# driver_board.net
KiCad netlist of a schematic drawn in EAGLE
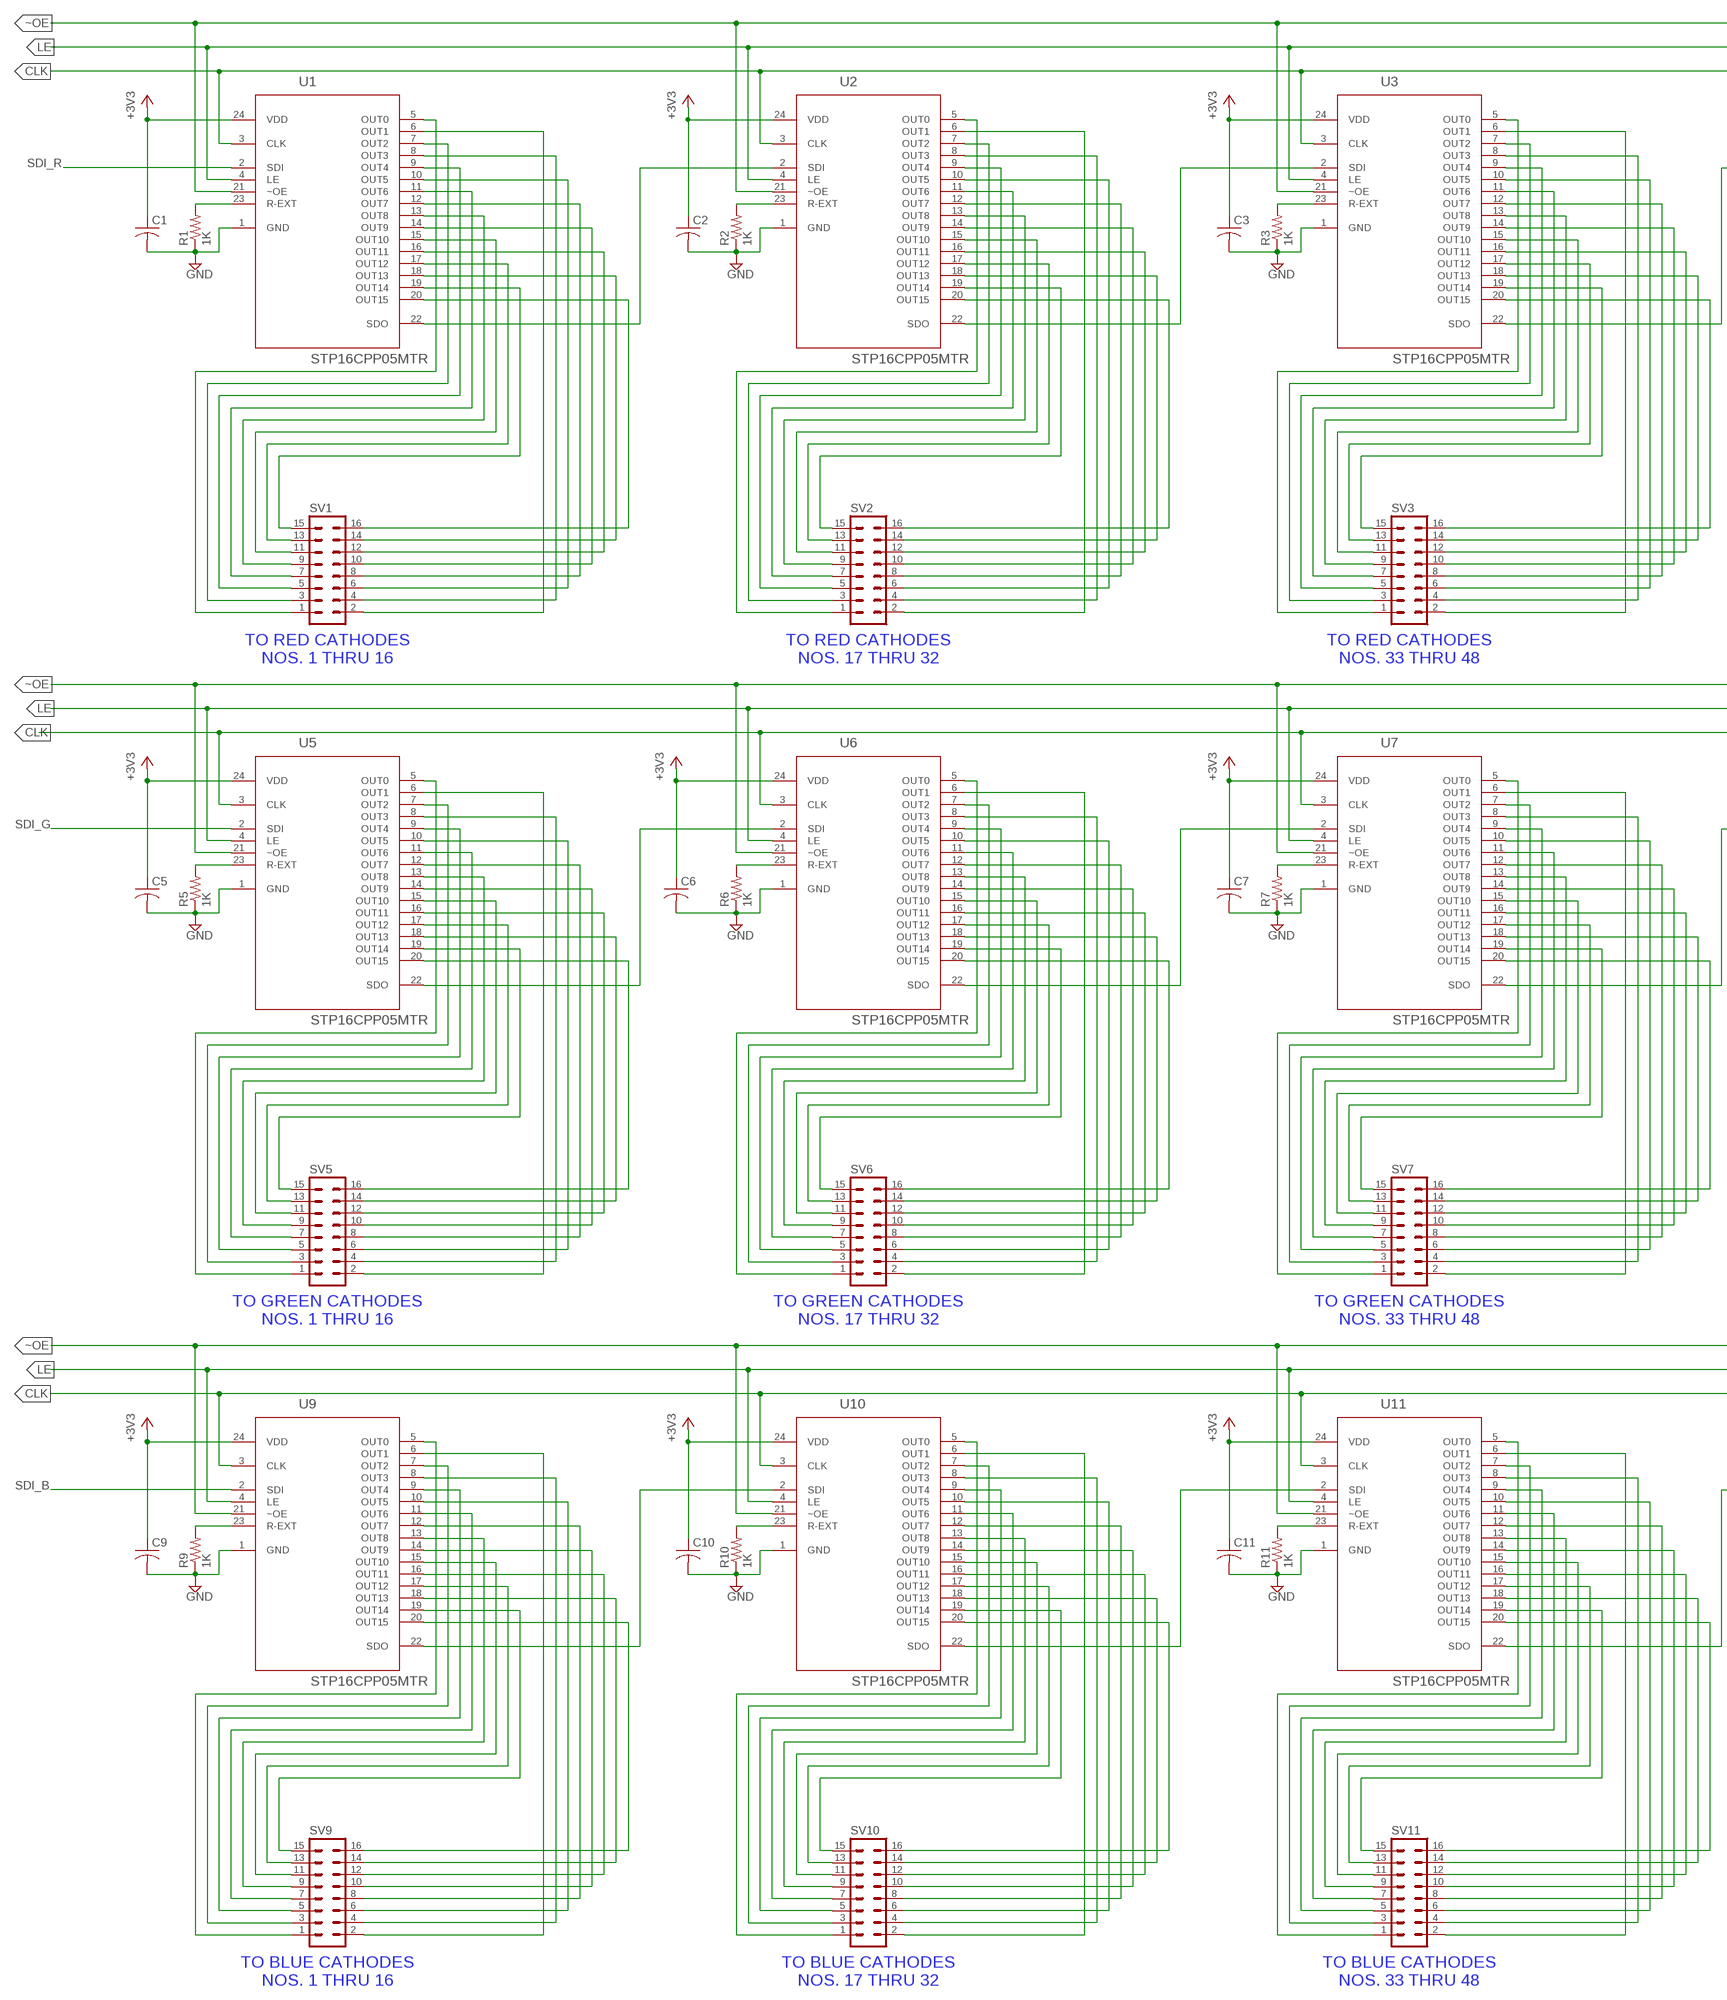
[diagram p0: schematic, sheet 1, part 1 of 2]
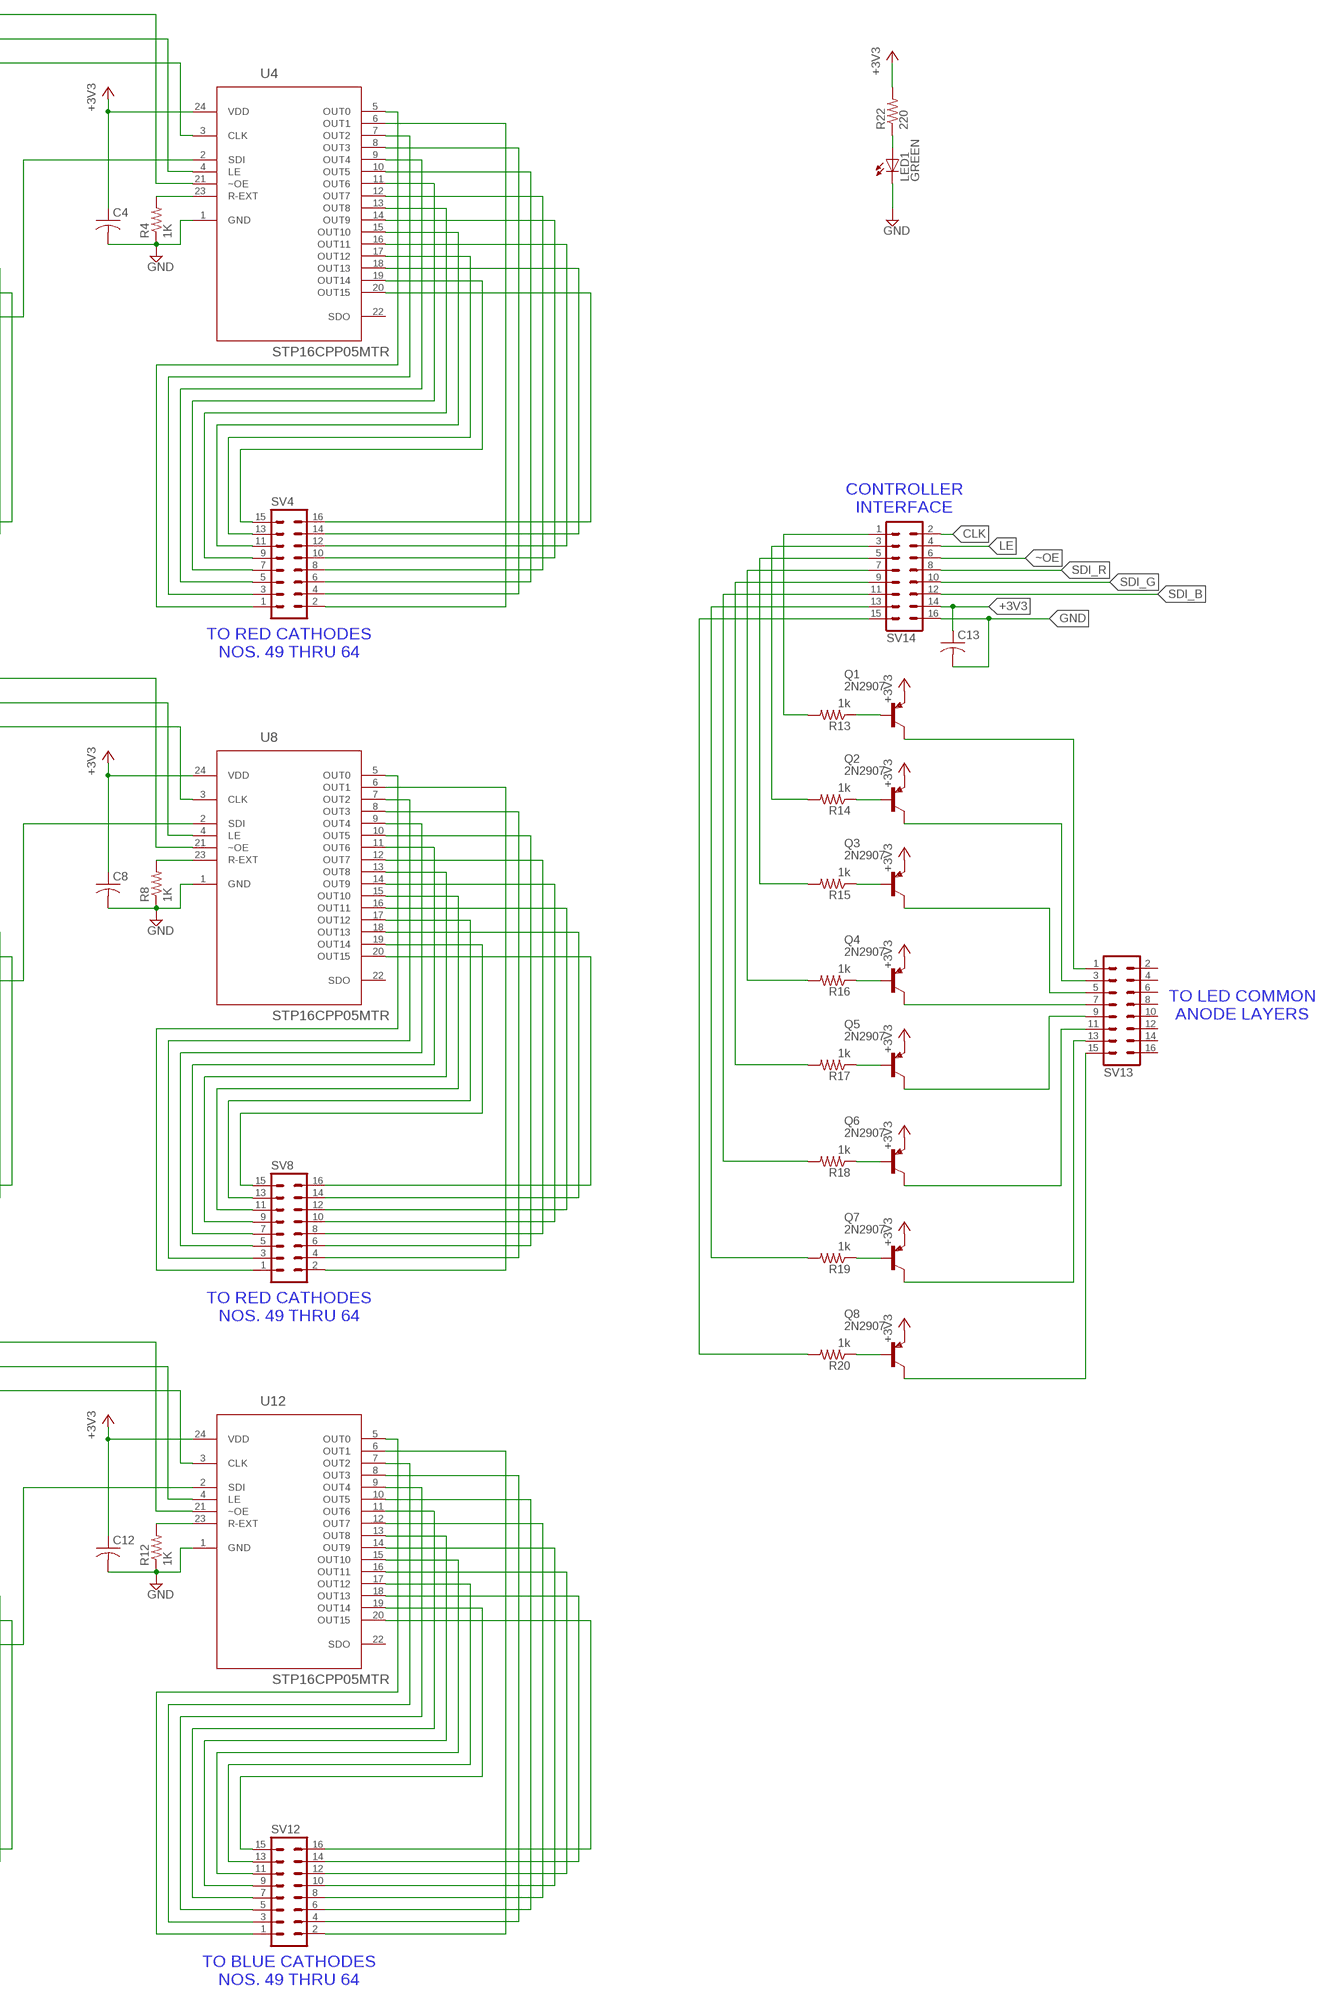
[diagram p1: schematic, sheet 1, part 2 of 2]

(export (version "E")
  (design (tool "Eeschema 10.0.6"))
  (components
    (comp (ref "C1")
      (value "C-USC0805")
      (footprint "eagle-import:C0805")
      (fields (field (name "MF") "AVX CORPORATION") (field (name "MPN") "0805ZC105KAT2A"))
      (libsource (lib "eagle-import") (part "C-USC0805"))
    )
    (comp (ref "C2")
      (value "C-USC0805")
      (footprint "eagle-import:C0805")
      (fields (field (name "MF") "AVX CORPORATION") (field (name "MPN") "0805ZC105KAT2A"))
      (libsource (lib "eagle-import") (part "C-USC0805"))
    )
    (comp (ref "C3")
      (value "C-USC0805")
      (footprint "eagle-import:C0805")
      (fields (field (name "MF") "AVX CORPORATION") (field (name "MPN") "0805ZC105KAT2A"))
      (libsource (lib "eagle-import") (part "C-USC0805"))
    )
    (comp (ref "C4")
      (value "C-USC0805")
      (footprint "eagle-import:C0805")
      (fields (field (name "MF") "AVX CORPORATION") (field (name "MPN") "0805ZC105KAT2A"))
      (libsource (lib "eagle-import") (part "C-USC0805"))
    )
    (comp (ref "C5")
      (value "C-USC0805")
      (footprint "eagle-import:C0805")
      (fields (field (name "MF") "AVX CORPORATION") (field (name "MPN") "0805ZC105KAT2A"))
      (libsource (lib "eagle-import") (part "C-USC0805"))
    )
    (comp (ref "C6")
      (value "C-USC0805")
      (footprint "eagle-import:C0805")
      (fields (field (name "MF") "AVX CORPORATION") (field (name "MPN") "0805ZC105KAT2A"))
      (libsource (lib "eagle-import") (part "C-USC0805"))
    )
    (comp (ref "C7")
      (value "C-USC0805")
      (footprint "eagle-import:C0805")
      (fields (field (name "MF") "AVX CORPORATION") (field (name "MPN") "0805ZC105KAT2A"))
      (libsource (lib "eagle-import") (part "C-USC0805"))
    )
    (comp (ref "C8")
      (value "C-USC0805")
      (footprint "eagle-import:C0805")
      (fields (field (name "MF") "AVX CORPORATION") (field (name "MPN") "0805ZC105KAT2A"))
      (libsource (lib "eagle-import") (part "C-USC0805"))
    )
    (comp (ref "C9")
      (value "C-USC0805")
      (footprint "eagle-import:C0805")
      (fields (field (name "MF") "AVX CORPORATION") (field (name "MPN") "0805ZC105KAT2A"))
      (libsource (lib "eagle-import") (part "C-USC0805"))
    )
    (comp (ref "C10")
      (value "C-USC0805")
      (footprint "eagle-import:C0805")
      (fields (field (name "MF") "AVX CORPORATION") (field (name "MPN") "0805ZC105KAT2A"))
      (libsource (lib "eagle-import") (part "C-USC0805"))
    )
    (comp (ref "C11")
      (value "C-USC0805")
      (footprint "eagle-import:C0805")
      (fields (field (name "MF") "AVX CORPORATION") (field (name "MPN") "0805ZC105KAT2A"))
      (libsource (lib "eagle-import") (part "C-USC0805"))
    )
    (comp (ref "C12")
      (value "C-USC0805")
      (footprint "eagle-import:C0805")
      (fields (field (name "MF") "AVX CORPORATION") (field (name "MPN") "0805ZC105KAT2A"))
      (libsource (lib "eagle-import") (part "C-USC0805"))
    )
    (comp (ref "C13")
      (value "C-USC0805")
      (footprint "eagle-import:C0805")
      (fields (field (name "MF") "AVX CORPORATION") (field (name "MPN") "0805ZC105KAT2A"))
      (libsource (lib "eagle-import") (part "C-USC0805"))
    )
    (comp (ref "LED1")
      (value "GREEN")
      (footprint "eagle-import:LED5MM")
      (fields (field (name "MF") "SLI (CML/IDI)") (field (name "MPN") "CMD17-21VGD/TR8"))
      (libsource (lib "eagle-import") (part "LED5MM"))
    )
    (comp (ref "Q1")
      (value "2N2907")
      (footprint "eagle-import:TO92-EBC-OVAL")
      (fields (field (name "MF") "ON SEMICONDUCTOR") (field (name "MPN") "TIP32BG"))
      (libsource (lib "eagle-import") (part "2N2907"))
    )
    (comp (ref "Q2")
      (value "2N2907")
      (footprint "eagle-import:TO92-EBC-OVAL")
      (fields (field (name "MF") "ON SEMICONDUCTOR") (field (name "MPN") "TIP32BG"))
      (libsource (lib "eagle-import") (part "2N2907"))
    )
    (comp (ref "Q3")
      (value "2N2907")
      (footprint "eagle-import:TO92-EBC-OVAL")
      (fields (field (name "MF") "ON SEMICONDUCTOR") (field (name "MPN") "TIP32BG"))
      (libsource (lib "eagle-import") (part "2N2907"))
    )
    (comp (ref "Q4")
      (value "2N2907")
      (footprint "eagle-import:TO92-EBC-OVAL")
      (fields (field (name "MF") "ON SEMICONDUCTOR") (field (name "MPN") "TIP32BG"))
      (libsource (lib "eagle-import") (part "2N2907"))
    )
    (comp (ref "Q5")
      (value "2N2907")
      (footprint "eagle-import:TO92-EBC-OVAL")
      (fields (field (name "MF") "ON SEMICONDUCTOR") (field (name "MPN") "TIP32BG"))
      (libsource (lib "eagle-import") (part "2N2907"))
    )
    (comp (ref "Q6")
      (value "2N2907")
      (footprint "eagle-import:TO92-EBC-OVAL")
      (fields (field (name "MF") "ON SEMICONDUCTOR") (field (name "MPN") "TIP32BG"))
      (libsource (lib "eagle-import") (part "2N2907"))
    )
    (comp (ref "Q7")
      (value "2N2907")
      (footprint "eagle-import:TO92-EBC-OVAL")
      (fields (field (name "MF") "ON SEMICONDUCTOR") (field (name "MPN") "TIP32BG"))
      (libsource (lib "eagle-import") (part "2N2907"))
    )
    (comp (ref "Q8")
      (value "2N2907")
      (footprint "eagle-import:TO92-EBC-OVAL")
      (fields (field (name "MF") "ON SEMICONDUCTOR") (field (name "MPN") "TIP32BG"))
      (libsource (lib "eagle-import") (part "2N2907"))
    )
    (comp (ref "R1")
      (value "1K")
      (footprint "eagle-import:R0805")
      (fields (field (name "MPN") "MC01W080511K"))
      (libsource (lib "eagle-import") (part "R-US_R0805"))
    )
    (comp (ref "R2")
      (value "1K")
      (footprint "eagle-import:R0805")
      (fields (field (name "MPN") "MC01W080511K"))
      (libsource (lib "eagle-import") (part "R-US_R0805"))
    )
    (comp (ref "R3")
      (value "1K")
      (footprint "eagle-import:R0805")
      (fields (field (name "MPN") "MC01W080511K"))
      (libsource (lib "eagle-import") (part "R-US_R0805"))
    )
    (comp (ref "R4")
      (value "1K")
      (footprint "eagle-import:R0805")
      (fields (field (name "MPN") "MC01W080511K"))
      (libsource (lib "eagle-import") (part "R-US_R0805"))
    )
    (comp (ref "R5")
      (value "1K")
      (footprint "eagle-import:R0805")
      (fields (field (name "MPN") "MC01W080511K"))
      (libsource (lib "eagle-import") (part "R-US_R0805"))
    )
    (comp (ref "R6")
      (value "1K")
      (footprint "eagle-import:R0805")
      (fields (field (name "MPN") "MC01W080511K"))
      (libsource (lib "eagle-import") (part "R-US_R0805"))
    )
    (comp (ref "R7")
      (value "1K")
      (footprint "eagle-import:R0805")
      (fields (field (name "MPN") "MC01W080511K"))
      (libsource (lib "eagle-import") (part "R-US_R0805"))
    )
    (comp (ref "R8")
      (value "1K")
      (footprint "eagle-import:R0805")
      (fields (field (name "MPN") "MC01W080511K"))
      (libsource (lib "eagle-import") (part "R-US_R0805"))
    )
    (comp (ref "R9")
      (value "1K")
      (footprint "eagle-import:R0805")
      (fields (field (name "MPN") "MC01W080511K"))
      (libsource (lib "eagle-import") (part "R-US_R0805"))
    )
    (comp (ref "R10")
      (value "1K")
      (footprint "eagle-import:R0805")
      (fields (field (name "MPN") "MC01W080511K"))
      (libsource (lib "eagle-import") (part "R-US_R0805"))
    )
    (comp (ref "R11")
      (value "1K")
      (footprint "eagle-import:R0805")
      (fields (field (name "MPN") "MC01W080511K"))
      (libsource (lib "eagle-import") (part "R-US_R0805"))
    )
    (comp (ref "R12")
      (value "1K")
      (footprint "eagle-import:R0805")
      (fields (field (name "MPN") "MC01W080511K"))
      (libsource (lib "eagle-import") (part "R-US_R0805"))
    )
    (comp (ref "R13")
      (value "1k")
      (footprint "eagle-import:R0805")
      (libsource (lib "eagle-import") (part "R-US_R0805"))
    )
    (comp (ref "R14")
      (value "1k")
      (footprint "eagle-import:R0805")
      (libsource (lib "eagle-import") (part "R-US_R0805"))
    )
    (comp (ref "R15")
      (value "1k")
      (footprint "eagle-import:R0805")
      (libsource (lib "eagle-import") (part "R-US_R0805"))
    )
    (comp (ref "R16")
      (value "1k")
      (footprint "eagle-import:R0805")
      (libsource (lib "eagle-import") (part "R-US_R0805"))
    )
    (comp (ref "R17")
      (value "1k")
      (footprint "eagle-import:R0805")
      (libsource (lib "eagle-import") (part "R-US_R0805"))
    )
    (comp (ref "R18")
      (value "1k")
      (footprint "eagle-import:R0805")
      (libsource (lib "eagle-import") (part "R-US_R0805"))
    )
    (comp (ref "R19")
      (value "1k")
      (footprint "eagle-import:R0805")
      (libsource (lib "eagle-import") (part "R-US_R0805"))
    )
    (comp (ref "R20")
      (value "1k")
      (footprint "eagle-import:R0805")
      (libsource (lib "eagle-import") (part "R-US_R0805"))
    )
    (comp (ref "R22")
      (value "220")
      (footprint "eagle-import:R0805")
      (fields (field (name "MPN") "MCHP05W4F2200T5E"))
      (libsource (lib "eagle-import") (part "R-US_R0805"))
    )
    (comp (ref "SV1")
      (value "16PL")
      (footprint "eagle-import:16PL")
      (fields (field (name "MF") "FARNELL") (field (name "MPN") "008380016000010"))
      (libsource (lib "eagle-import") (part "16PL"))
    )
    (comp (ref "SV2")
      (value "16PL")
      (footprint "eagle-import:16PL")
      (fields (field (name "MF") "FARNELL") (field (name "MPN") "008380016000010"))
      (libsource (lib "eagle-import") (part "16PL"))
    )
    (comp (ref "SV3")
      (value "16PL")
      (footprint "eagle-import:16PL")
      (fields (field (name "MF") "FARNELL") (field (name "MPN") "008380016000010"))
      (libsource (lib "eagle-import") (part "16PL"))
    )
    (comp (ref "SV4")
      (value "16PL")
      (footprint "eagle-import:16PL")
      (fields (field (name "MF") "FARNELL") (field (name "MPN") "008380016000010"))
      (libsource (lib "eagle-import") (part "16PL"))
    )
    (comp (ref "SV5")
      (value "16PL")
      (footprint "eagle-import:16PL")
      (fields (field (name "MF") "FARNELL") (field (name "MPN") "008380016000010"))
      (libsource (lib "eagle-import") (part "16PL"))
    )
    (comp (ref "SV6")
      (value "16PL")
      (footprint "eagle-import:16PL")
      (fields (field (name "MF") "FARNELL") (field (name "MPN") "008380016000010"))
      (libsource (lib "eagle-import") (part "16PL"))
    )
    (comp (ref "SV7")
      (value "16PL")
      (footprint "eagle-import:16PL")
      (fields (field (name "MF") "FARNELL") (field (name "MPN") "008380016000010"))
      (libsource (lib "eagle-import") (part "16PL"))
    )
    (comp (ref "SV8")
      (value "16PL")
      (footprint "eagle-import:16PL")
      (fields (field (name "MF") "FARNELL") (field (name "MPN") "008380016000010"))
      (libsource (lib "eagle-import") (part "16PL"))
    )
    (comp (ref "SV9")
      (value "16PL")
      (footprint "eagle-import:16PL")
      (fields (field (name "MF") "FARNELL") (field (name "MPN") "008380016000010"))
      (libsource (lib "eagle-import") (part "16PL"))
    )
    (comp (ref "SV10")
      (value "16PL")
      (footprint "eagle-import:16PL")
      (fields (field (name "MF") "FARNELL") (field (name "MPN") "008380016000010"))
      (libsource (lib "eagle-import") (part "16PL"))
    )
    (comp (ref "SV11")
      (value "16PL")
      (footprint "eagle-import:16PL")
      (fields (field (name "MF") "FARNELL") (field (name "MPN") "008380016000010"))
      (libsource (lib "eagle-import") (part "16PL"))
    )
    (comp (ref "SV12")
      (value "16PL")
      (footprint "eagle-import:16PL")
      (fields (field (name "MF") "FARNELL") (field (name "MPN") "008380016000010"))
      (libsource (lib "eagle-import") (part "16PL"))
    )
    (comp (ref "SV13")
      (value "16PL")
      (footprint "eagle-import:16PL")
      (fields (field (name "MF") "FARNELL") (field (name "MPN") "008380016000010"))
      (libsource (lib "eagle-import") (part "16PL"))
    )
    (comp (ref "SV14")
      (value "16PL")
      (footprint "eagle-import:16PL")
      (fields (field (name "MF") "FARNELL") (field (name "MPN") "008380016000010"))
      (libsource (lib "eagle-import") (part "16PL"))
    )
    (comp (ref "U1")
      (value "STP16CPP05MTR")
      (footprint "eagle-import:SOIC127P1032X265-24N")
      (libsource (lib "eagle-import") (part "STP16CPP05MTR"))
    )
    (comp (ref "U2")
      (value "STP16CPP05MTR")
      (footprint "eagle-import:SOIC127P1032X265-24N")
      (libsource (lib "eagle-import") (part "STP16CPP05MTR"))
    )
    (comp (ref "U3")
      (value "STP16CPP05MTR")
      (footprint "eagle-import:SOIC127P1032X265-24N")
      (libsource (lib "eagle-import") (part "STP16CPP05MTR"))
    )
    (comp (ref "U4")
      (value "STP16CPP05MTR")
      (footprint "eagle-import:SOIC127P1032X265-24N")
      (libsource (lib "eagle-import") (part "STP16CPP05MTR"))
    )
    (comp (ref "U5")
      (value "STP16CPP05MTR")
      (footprint "eagle-import:SOIC127P1032X265-24N")
      (libsource (lib "eagle-import") (part "STP16CPP05MTR"))
    )
    (comp (ref "U6")
      (value "STP16CPP05MTR")
      (footprint "eagle-import:SOIC127P1032X265-24N")
      (libsource (lib "eagle-import") (part "STP16CPP05MTR"))
    )
    (comp (ref "U7")
      (value "STP16CPP05MTR")
      (footprint "eagle-import:SOIC127P1032X265-24N")
      (libsource (lib "eagle-import") (part "STP16CPP05MTR"))
    )
    (comp (ref "U8")
      (value "STP16CPP05MTR")
      (footprint "eagle-import:SOIC127P1032X265-24N")
      (libsource (lib "eagle-import") (part "STP16CPP05MTR"))
    )
    (comp (ref "U9")
      (value "STP16CPP05MTR")
      (footprint "eagle-import:SOIC127P1032X265-24N")
      (libsource (lib "eagle-import") (part "STP16CPP05MTR"))
    )
    (comp (ref "U10")
      (value "STP16CPP05MTR")
      (footprint "eagle-import:SOIC127P1032X265-24N")
      (libsource (lib "eagle-import") (part "STP16CPP05MTR"))
    )
    (comp (ref "U11")
      (value "STP16CPP05MTR")
      (footprint "eagle-import:SOIC127P1032X265-24N")
      (libsource (lib "eagle-import") (part "STP16CPP05MTR"))
    )
    (comp (ref "U12")
      (value "STP16CPP05MTR")
      (footprint "eagle-import:SOIC127P1032X265-24N")
      (libsource (lib "eagle-import") (part "STP16CPP05MTR"))
    )
  )
  (nets
    (net (code "1") (name "+3V3") (class "Default")
      (node (ref "C1") (pin "1") (pinfunction "1_1") (pintype "passive"))
      (node (ref "C10") (pin "1") (pinfunction "1_1") (pintype "passive"))
      (node (ref "C11") (pin "1") (pinfunction "1_1") (pintype "passive"))
      (node (ref "C12") (pin "1") (pinfunction "1_1") (pintype "passive"))
      (node (ref "C13") (pin "1") (pinfunction "1_1") (pintype "passive"))
      (node (ref "C2") (pin "1") (pinfunction "1_1") (pintype "passive"))
      (node (ref "C3") (pin "1") (pinfunction "1_1") (pintype "passive"))
      (node (ref "C4") (pin "1") (pinfunction "1_1") (pintype "passive"))
      (node (ref "C5") (pin "1") (pinfunction "1_1") (pintype "passive"))
      (node (ref "C6") (pin "1") (pinfunction "1_1") (pintype "passive"))
      (node (ref "C7") (pin "1") (pinfunction "1_1") (pintype "passive"))
      (node (ref "C8") (pin "1") (pinfunction "1_1") (pintype "passive"))
      (node (ref "C9") (pin "1") (pinfunction "1_1") (pintype "passive"))
      (node (ref "Q1") (pin "E") (pinfunction "E_E") (pintype "passive"))
      (node (ref "Q2") (pin "E") (pinfunction "E_E") (pintype "passive"))
      (node (ref "Q3") (pin "E") (pinfunction "E_E") (pintype "passive"))
      (node (ref "Q4") (pin "E") (pinfunction "E_E") (pintype "passive"))
      (node (ref "Q5") (pin "E") (pinfunction "E_E") (pintype "passive"))
      (node (ref "Q6") (pin "E") (pinfunction "E_E") (pintype "passive"))
      (node (ref "Q7") (pin "E") (pinfunction "E_E") (pintype "passive"))
      (node (ref "Q8") (pin "E") (pinfunction "E_E") (pintype "passive"))
      (node (ref "R22") (pin "2") (pinfunction "2_2") (pintype "passive"))
      (node (ref "SV14") (pin "14") (pinfunction "14_14") (pintype "passive"))
      (node (ref "U1") (pin "24") (pinfunction "VDD_24") (pintype "power_in"))
      (node (ref "U10") (pin "24") (pinfunction "VDD_24") (pintype "power_in"))
      (node (ref "U11") (pin "24") (pinfunction "VDD_24") (pintype "power_in"))
      (node (ref "U12") (pin "24") (pinfunction "VDD_24") (pintype "power_in"))
      (node (ref "U2") (pin "24") (pinfunction "VDD_24") (pintype "power_in"))
      (node (ref "U3") (pin "24") (pinfunction "VDD_24") (pintype "power_in"))
      (node (ref "U4") (pin "24") (pinfunction "VDD_24") (pintype "power_in"))
      (node (ref "U5") (pin "24") (pinfunction "VDD_24") (pintype "power_in"))
      (node (ref "U6") (pin "24") (pinfunction "VDD_24") (pintype "power_in"))
      (node (ref "U7") (pin "24") (pinfunction "VDD_24") (pintype "power_in"))
      (node (ref "U8") (pin "24") (pinfunction "VDD_24") (pintype "power_in"))
      (node (ref "U9") (pin "24") (pinfunction "VDD_24") (pintype "power_in"))
    )
    (net (code "2") (name "/~{OE}") (class "Default")
      (node (ref "SV14") (pin "6") (pinfunction "6_6") (pintype "passive"))
      (node (ref "U1") (pin "21") (pinfunction "~{OE}_21") (pintype "input"))
      (node (ref "U10") (pin "21") (pinfunction "~{OE}_21") (pintype "input"))
      (node (ref "U11") (pin "21") (pinfunction "~{OE}_21") (pintype "input"))
      (node (ref "U12") (pin "21") (pinfunction "~{OE}_21") (pintype "input"))
      (node (ref "U2") (pin "21") (pinfunction "~{OE}_21") (pintype "input"))
      (node (ref "U3") (pin "21") (pinfunction "~{OE}_21") (pintype "input"))
      (node (ref "U4") (pin "21") (pinfunction "~{OE}_21") (pintype "input"))
      (node (ref "U5") (pin "21") (pinfunction "~{OE}_21") (pintype "input"))
      (node (ref "U6") (pin "21") (pinfunction "~{OE}_21") (pintype "input"))
      (node (ref "U7") (pin "21") (pinfunction "~{OE}_21") (pintype "input"))
      (node (ref "U8") (pin "21") (pinfunction "~{OE}_21") (pintype "input"))
      (node (ref "U9") (pin "21") (pinfunction "~{OE}_21") (pintype "input"))
    )
    (net (code "3") (name "CLK") (class "Default")
      (node (ref "SV14") (pin "2") (pinfunction "2_2") (pintype "passive"))
      (node (ref "U1") (pin "3") (pinfunction "CLK_3") (pintype "input"))
      (node (ref "U10") (pin "3") (pinfunction "CLK_3") (pintype "input"))
      (node (ref "U11") (pin "3") (pinfunction "CLK_3") (pintype "input"))
      (node (ref "U12") (pin "3") (pinfunction "CLK_3") (pintype "input"))
      (node (ref "U2") (pin "3") (pinfunction "CLK_3") (pintype "input"))
      (node (ref "U3") (pin "3") (pinfunction "CLK_3") (pintype "input"))
      (node (ref "U4") (pin "3") (pinfunction "CLK_3") (pintype "input"))
      (node (ref "U5") (pin "3") (pinfunction "CLK_3") (pintype "input"))
      (node (ref "U6") (pin "3") (pinfunction "CLK_3") (pintype "input"))
      (node (ref "U7") (pin "3") (pinfunction "CLK_3") (pintype "input"))
      (node (ref "U8") (pin "3") (pinfunction "CLK_3") (pintype "input"))
      (node (ref "U9") (pin "3") (pinfunction "CLK_3") (pintype "input"))
    )
    (net (code "4") (name "GND") (class "Default")
      (node (ref "C1") (pin "2") (pinfunction "2_2") (pintype "passive"))
      (node (ref "C10") (pin "2") (pinfunction "2_2") (pintype "passive"))
      (node (ref "C11") (pin "2") (pinfunction "2_2") (pintype "passive"))
      (node (ref "C12") (pin "2") (pinfunction "2_2") (pintype "passive"))
      (node (ref "C13") (pin "2") (pinfunction "2_2") (pintype "passive"))
      (node (ref "C2") (pin "2") (pinfunction "2_2") (pintype "passive"))
      (node (ref "C3") (pin "2") (pinfunction "2_2") (pintype "passive"))
      (node (ref "C4") (pin "2") (pinfunction "2_2") (pintype "passive"))
      (node (ref "C5") (pin "2") (pinfunction "2_2") (pintype "passive"))
      (node (ref "C6") (pin "2") (pinfunction "2_2") (pintype "passive"))
      (node (ref "C7") (pin "2") (pinfunction "2_2") (pintype "passive"))
      (node (ref "C8") (pin "2") (pinfunction "2_2") (pintype "passive"))
      (node (ref "C9") (pin "2") (pinfunction "2_2") (pintype "passive"))
      (node (ref "LED1") (pin "K") (pinfunction "C_K") (pintype "passive"))
      (node (ref "R1") (pin "1") (pinfunction "1_1") (pintype "passive"))
      (node (ref "R10") (pin "1") (pinfunction "1_1") (pintype "passive"))
      (node (ref "R11") (pin "1") (pinfunction "1_1") (pintype "passive"))
      (node (ref "R12") (pin "1") (pinfunction "1_1") (pintype "passive"))
      (node (ref "R2") (pin "1") (pinfunction "1_1") (pintype "passive"))
      (node (ref "R3") (pin "1") (pinfunction "1_1") (pintype "passive"))
      (node (ref "R4") (pin "1") (pinfunction "1_1") (pintype "passive"))
      (node (ref "R5") (pin "1") (pinfunction "1_1") (pintype "passive"))
      (node (ref "R6") (pin "1") (pinfunction "1_1") (pintype "passive"))
      (node (ref "R7") (pin "1") (pinfunction "1_1") (pintype "passive"))
      (node (ref "R8") (pin "1") (pinfunction "1_1") (pintype "passive"))
      (node (ref "R9") (pin "1") (pinfunction "1_1") (pintype "passive"))
      (node (ref "SV14") (pin "16") (pinfunction "16_16") (pintype "passive"))
      (node (ref "U1") (pin "1") (pinfunction "GND_1") (pintype "passive"))
      (node (ref "U10") (pin "1") (pinfunction "GND_1") (pintype "passive"))
      (node (ref "U11") (pin "1") (pinfunction "GND_1") (pintype "passive"))
      (node (ref "U12") (pin "1") (pinfunction "GND_1") (pintype "passive"))
      (node (ref "U2") (pin "1") (pinfunction "GND_1") (pintype "passive"))
      (node (ref "U3") (pin "1") (pinfunction "GND_1") (pintype "passive"))
      (node (ref "U4") (pin "1") (pinfunction "GND_1") (pintype "passive"))
      (node (ref "U5") (pin "1") (pinfunction "GND_1") (pintype "passive"))
      (node (ref "U6") (pin "1") (pinfunction "GND_1") (pintype "passive"))
      (node (ref "U7") (pin "1") (pinfunction "GND_1") (pintype "passive"))
      (node (ref "U8") (pin "1") (pinfunction "GND_1") (pintype "passive"))
      (node (ref "U9") (pin "1") (pinfunction "GND_1") (pintype "passive"))
    )
    (net (code "5") (name "LE") (class "Default")
      (node (ref "SV14") (pin "4") (pinfunction "4_4") (pintype "passive"))
      (node (ref "U1") (pin "4") (pinfunction "LE_4") (pintype "input"))
      (node (ref "U10") (pin "4") (pinfunction "LE_4") (pintype "input"))
      (node (ref "U11") (pin "4") (pinfunction "LE_4") (pintype "input"))
      (node (ref "U12") (pin "4") (pinfunction "LE_4") (pintype "input"))
      (node (ref "U2") (pin "4") (pinfunction "LE_4") (pintype "input"))
      (node (ref "U3") (pin "4") (pinfunction "LE_4") (pintype "input"))
      (node (ref "U4") (pin "4") (pinfunction "LE_4") (pintype "input"))
      (node (ref "U5") (pin "4") (pinfunction "LE_4") (pintype "input"))
      (node (ref "U6") (pin "4") (pinfunction "LE_4") (pintype "input"))
      (node (ref "U7") (pin "4") (pinfunction "LE_4") (pintype "input"))
      (node (ref "U8") (pin "4") (pinfunction "LE_4") (pintype "input"))
      (node (ref "U9") (pin "4") (pinfunction "LE_4") (pintype "input"))
    )
    (net (code "6") (name "Net-(LED1-PadA)") (class "Default")
      (node (ref "LED1") (pin "A") (pinfunction "A_A") (pintype "passive"))
      (node (ref "R22") (pin "1") (pinfunction "1_1") (pintype "passive"))
    )
    (net (code "7") (name "Net-(Q1-PadB)") (class "Default")
      (node (ref "Q1") (pin "B") (pinfunction "B_B") (pintype "passive"))
      (node (ref "R13") (pin "1") (pinfunction "1_1") (pintype "passive"))
    )
    (net (code "8") (name "Net-(Q1-PadC)") (class "Default")
      (node (ref "Q1") (pin "C") (pinfunction "C_C") (pintype "passive"))
      (node (ref "SV13") (pin "1") (pinfunction "1_1") (pintype "passive"))
    )
    (net (code "9") (name "Net-(Q2-PadB)") (class "Default")
      (node (ref "Q2") (pin "B") (pinfunction "B_B") (pintype "passive"))
      (node (ref "R14") (pin "1") (pinfunction "1_1") (pintype "passive"))
    )
    (net (code "10") (name "Net-(Q2-PadC)") (class "Default")
      (node (ref "Q2") (pin "C") (pinfunction "C_C") (pintype "passive"))
      (node (ref "SV13") (pin "3") (pinfunction "3_3") (pintype "passive"))
    )
    (net (code "11") (name "Net-(Q3-PadB)") (class "Default")
      (node (ref "Q3") (pin "B") (pinfunction "B_B") (pintype "passive"))
      (node (ref "R15") (pin "1") (pinfunction "1_1") (pintype "passive"))
    )
    (net (code "12") (name "Net-(Q3-PadC)") (class "Default")
      (node (ref "Q3") (pin "C") (pinfunction "C_C") (pintype "passive"))
      (node (ref "SV13") (pin "5") (pinfunction "5_5") (pintype "passive"))
    )
    (net (code "13") (name "Net-(Q4-PadB)") (class "Default")
      (node (ref "Q4") (pin "B") (pinfunction "B_B") (pintype "passive"))
      (node (ref "R16") (pin "1") (pinfunction "1_1") (pintype "passive"))
    )
    (net (code "14") (name "Net-(Q4-PadC)") (class "Default")
      (node (ref "Q4") (pin "C") (pinfunction "C_C") (pintype "passive"))
      (node (ref "SV13") (pin "7") (pinfunction "7_7") (pintype "passive"))
    )
    (net (code "15") (name "Net-(Q5-PadB)") (class "Default")
      (node (ref "Q5") (pin "B") (pinfunction "B_B") (pintype "passive"))
      (node (ref "R17") (pin "1") (pinfunction "1_1") (pintype "passive"))
    )
    (net (code "16") (name "Net-(Q5-PadC)") (class "Default")
      (node (ref "Q5") (pin "C") (pinfunction "C_C") (pintype "passive"))
      (node (ref "SV13") (pin "9") (pinfunction "9_9") (pintype "passive"))
    )
    (net (code "17") (name "Net-(Q6-PadB)") (class "Default")
      (node (ref "Q6") (pin "B") (pinfunction "B_B") (pintype "passive"))
      (node (ref "R18") (pin "1") (pinfunction "1_1") (pintype "passive"))
    )
    (net (code "18") (name "Net-(Q6-PadC)") (class "Default")
      (node (ref "Q6") (pin "C") (pinfunction "C_C") (pintype "passive"))
      (node (ref "SV13") (pin "11") (pinfunction "11_11") (pintype "passive"))
    )
    (net (code "19") (name "Net-(Q7-PadB)") (class "Default")
      (node (ref "Q7") (pin "B") (pinfunction "B_B") (pintype "passive"))
      (node (ref "R19") (pin "1") (pinfunction "1_1") (pintype "passive"))
    )
    (net (code "20") (name "Net-(Q7-PadC)") (class "Default")
      (node (ref "Q7") (pin "C") (pinfunction "C_C") (pintype "passive"))
      (node (ref "SV13") (pin "13") (pinfunction "13_13") (pintype "passive"))
    )
    (net (code "21") (name "Net-(Q8-PadB)") (class "Default")
      (node (ref "Q8") (pin "B") (pinfunction "B_B") (pintype "passive"))
      (node (ref "R20") (pin "1") (pinfunction "1_1") (pintype "passive"))
    )
    (net (code "22") (name "Net-(Q8-PadC)") (class "Default")
      (node (ref "Q8") (pin "C") (pinfunction "C_C") (pintype "passive"))
      (node (ref "SV13") (pin "15") (pinfunction "15_15") (pintype "passive"))
    )
    (net (code "23") (name "Net-(R13-Pad2)") (class "Default")
      (node (ref "R13") (pin "2") (pinfunction "2_2") (pintype "passive"))
      (node (ref "SV14") (pin "1") (pinfunction "1_1") (pintype "passive"))
    )
    (net (code "24") (name "Net-(R14-Pad2)") (class "Default")
      (node (ref "R14") (pin "2") (pinfunction "2_2") (pintype "passive"))
      (node (ref "SV14") (pin "3") (pinfunction "3_3") (pintype "passive"))
    )
    (net (code "25") (name "Net-(R15-Pad2)") (class "Default")
      (node (ref "R15") (pin "2") (pinfunction "2_2") (pintype "passive"))
      (node (ref "SV14") (pin "5") (pinfunction "5_5") (pintype "passive"))
    )
    (net (code "26") (name "Net-(R16-Pad2)") (class "Default")
      (node (ref "R16") (pin "2") (pinfunction "2_2") (pintype "passive"))
      (node (ref "SV14") (pin "7") (pinfunction "7_7") (pintype "passive"))
    )
    (net (code "27") (name "Net-(R17-Pad2)") (class "Default")
      (node (ref "R17") (pin "2") (pinfunction "2_2") (pintype "passive"))
      (node (ref "SV14") (pin "9") (pinfunction "9_9") (pintype "passive"))
    )
    (net (code "28") (name "Net-(R18-Pad2)") (class "Default")
      (node (ref "R18") (pin "2") (pinfunction "2_2") (pintype "passive"))
      (node (ref "SV14") (pin "11") (pinfunction "11_11") (pintype "passive"))
    )
    (net (code "29") (name "Net-(R19-Pad2)") (class "Default")
      (node (ref "R19") (pin "2") (pinfunction "2_2") (pintype "passive"))
      (node (ref "SV14") (pin "13") (pinfunction "13_13") (pintype "passive"))
    )
    (net (code "30") (name "Net-(R20-Pad2)") (class "Default")
      (node (ref "R20") (pin "2") (pinfunction "2_2") (pintype "passive"))
      (node (ref "SV14") (pin "15") (pinfunction "15_15") (pintype "passive"))
    )
    (net (code "31") (name "Net-(U1-OUT0)") (class "Default")
      (node (ref "SV1") (pin "1") (pinfunction "1_1") (pintype "passive"))
      (node (ref "U1") (pin "5") (pinfunction "OUT0_5") (pintype "output"))
    )
    (net (code "32") (name "Net-(U1-OUT1)") (class "Default")
      (node (ref "SV1") (pin "2") (pinfunction "2_2") (pintype "passive"))
      (node (ref "U1") (pin "6") (pinfunction "OUT1_6") (pintype "output"))
    )
    (net (code "33") (name "Net-(U1-OUT2)") (class "Default")
      (node (ref "SV1") (pin "3") (pinfunction "3_3") (pintype "passive"))
      (node (ref "U1") (pin "7") (pinfunction "OUT2_7") (pintype "output"))
    )
    (net (code "34") (name "Net-(U1-OUT3)") (class "Default")
      (node (ref "SV1") (pin "4") (pinfunction "4_4") (pintype "passive"))
      (node (ref "U1") (pin "8") (pinfunction "OUT3_8") (pintype "output"))
    )
    (net (code "35") (name "Net-(U1-OUT4)") (class "Default")
      (node (ref "SV1") (pin "5") (pinfunction "5_5") (pintype "passive"))
      (node (ref "U1") (pin "9") (pinfunction "OUT4_9") (pintype "output"))
    )
    (net (code "36") (name "Net-(U1-OUT5)") (class "Default")
      (node (ref "SV1") (pin "6") (pinfunction "6_6") (pintype "passive"))
      (node (ref "U1") (pin "10") (pinfunction "OUT5_10") (pintype "output"))
    )
    (net (code "37") (name "Net-(U1-OUT6)") (class "Default")
      (node (ref "SV1") (pin "7") (pinfunction "7_7") (pintype "passive"))
      (node (ref "U1") (pin "11") (pinfunction "OUT6_11") (pintype "output"))
    )
    (net (code "38") (name "Net-(U1-OUT7)") (class "Default")
      (node (ref "SV1") (pin "8") (pinfunction "8_8") (pintype "passive"))
      (node (ref "U1") (pin "12") (pinfunction "OUT7_12") (pintype "output"))
    )
    (net (code "39") (name "Net-(U1-OUT8)") (class "Default")
      (node (ref "SV1") (pin "9") (pinfunction "9_9") (pintype "passive"))
      (node (ref "U1") (pin "13") (pinfunction "OUT8_13") (pintype "output"))
    )
    (net (code "40") (name "Net-(U1-OUT9)") (class "Default")
      (node (ref "SV1") (pin "10") (pinfunction "10_10") (pintype "passive"))
      (node (ref "U1") (pin "14") (pinfunction "OUT9_14") (pintype "output"))
    )
    (net (code "41") (name "Net-(U1-OUT10)") (class "Default")
      (node (ref "SV1") (pin "11") (pinfunction "11_11") (pintype "passive"))
      (node (ref "U1") (pin "15") (pinfunction "OUT10_15") (pintype "output"))
    )
    (net (code "42") (name "Net-(U1-OUT11)") (class "Default")
      (node (ref "SV1") (pin "12") (pinfunction "12_12") (pintype "passive"))
      (node (ref "U1") (pin "16") (pinfunction "OUT11_16") (pintype "output"))
    )
    (net (code "43") (name "Net-(U1-OUT12)") (class "Default")
      (node (ref "SV1") (pin "13") (pinfunction "13_13") (pintype "passive"))
      (node (ref "U1") (pin "17") (pinfunction "OUT12_17") (pintype "output"))
    )
    (net (code "44") (name "Net-(U1-OUT13)") (class "Default")
      (node (ref "SV1") (pin "14") (pinfunction "14_14") (pintype "passive"))
      (node (ref "U1") (pin "18") (pinfunction "OUT13_18") (pintype "output"))
    )
    (net (code "45") (name "Net-(U1-OUT14)") (class "Default")
      (node (ref "SV1") (pin "15") (pinfunction "15_15") (pintype "passive"))
      (node (ref "U1") (pin "19") (pinfunction "OUT14_19") (pintype "output"))
    )
    (net (code "46") (name "Net-(U1-OUT15)") (class "Default")
      (node (ref "SV1") (pin "16") (pinfunction "16_16") (pintype "passive"))
      (node (ref "U1") (pin "20") (pinfunction "OUT15_20") (pintype "output"))
    )
    (net (code "47") (name "Net-(U1-R-EXT)") (class "Default")
      (node (ref "R1") (pin "2") (pinfunction "2_2") (pintype "passive"))
      (node (ref "U1") (pin "23") (pinfunction "R-EXT_23") (pintype "input"))
    )
    (net (code "48") (name "Net-(U1-SDO)") (class "Default")
      (node (ref "U1") (pin "22") (pinfunction "SDO_22") (pintype "output"))
      (node (ref "U2") (pin "2") (pinfunction "SDI_2") (pintype "input"))
    )
    (net (code "49") (name "Net-(U2-OUT0)") (class "Default")
      (node (ref "SV2") (pin "1") (pinfunction "1_1") (pintype "passive"))
      (node (ref "U2") (pin "5") (pinfunction "OUT0_5") (pintype "output"))
    )
    (net (code "50") (name "Net-(U2-OUT1)") (class "Default")
      (node (ref "SV2") (pin "2") (pinfunction "2_2") (pintype "passive"))
      (node (ref "U2") (pin "6") (pinfunction "OUT1_6") (pintype "output"))
    )
    (net (code "51") (name "Net-(U2-OUT2)") (class "Default")
      (node (ref "SV2") (pin "3") (pinfunction "3_3") (pintype "passive"))
      (node (ref "U2") (pin "7") (pinfunction "OUT2_7") (pintype "output"))
    )
    (net (code "52") (name "Net-(U2-OUT3)") (class "Default")
      (node (ref "SV2") (pin "4") (pinfunction "4_4") (pintype "passive"))
      (node (ref "U2") (pin "8") (pinfunction "OUT3_8") (pintype "output"))
    )
    (net (code "53") (name "Net-(U2-OUT4)") (class "Default")
      (node (ref "SV2") (pin "5") (pinfunction "5_5") (pintype "passive"))
      (node (ref "U2") (pin "9") (pinfunction "OUT4_9") (pintype "output"))
    )
    (net (code "54") (name "Net-(U2-OUT5)") (class "Default")
      (node (ref "SV2") (pin "6") (pinfunction "6_6") (pintype "passive"))
      (node (ref "U2") (pin "10") (pinfunction "OUT5_10") (pintype "output"))
    )
    (net (code "55") (name "Net-(U2-OUT6)") (class "Default")
      (node (ref "SV2") (pin "7") (pinfunction "7_7") (pintype "passive"))
      (node (ref "U2") (pin "11") (pinfunction "OUT6_11") (pintype "output"))
    )
    (net (code "56") (name "Net-(U2-OUT7)") (class "Default")
      (node (ref "SV2") (pin "8") (pinfunction "8_8") (pintype "passive"))
      (node (ref "U2") (pin "12") (pinfunction "OUT7_12") (pintype "output"))
    )
    (net (code "57") (name "Net-(U2-OUT8)") (class "Default")
      (node (ref "SV2") (pin "9") (pinfunction "9_9") (pintype "passive"))
      (node (ref "U2") (pin "13") (pinfunction "OUT8_13") (pintype "output"))
    )
    (net (code "58") (name "Net-(U2-OUT9)") (class "Default")
      (node (ref "SV2") (pin "10") (pinfunction "10_10") (pintype "passive"))
      (node (ref "U2") (pin "14") (pinfunction "OUT9_14") (pintype "output"))
    )
    (net (code "59") (name "Net-(U2-OUT10)") (class "Default")
      (node (ref "SV2") (pin "11") (pinfunction "11_11") (pintype "passive"))
      (node (ref "U2") (pin "15") (pinfunction "OUT10_15") (pintype "output"))
    )
    (net (code "60") (name "Net-(U2-OUT11)") (class "Default")
      (node (ref "SV2") (pin "12") (pinfunction "12_12") (pintype "passive"))
      (node (ref "U2") (pin "16") (pinfunction "OUT11_16") (pintype "output"))
    )
    (net (code "61") (name "Net-(U2-OUT12)") (class "Default")
      (node (ref "SV2") (pin "13") (pinfunction "13_13") (pintype "passive"))
      (node (ref "U2") (pin "17") (pinfunction "OUT12_17") (pintype "output"))
    )
    (net (code "62") (name "Net-(U2-OUT13)") (class "Default")
      (node (ref "SV2") (pin "14") (pinfunction "14_14") (pintype "passive"))
      (node (ref "U2") (pin "18") (pinfunction "OUT13_18") (pintype "output"))
    )
    (net (code "63") (name "Net-(U2-OUT14)") (class "Default")
      (node (ref "SV2") (pin "15") (pinfunction "15_15") (pintype "passive"))
      (node (ref "U2") (pin "19") (pinfunction "OUT14_19") (pintype "output"))
    )
    (net (code "64") (name "Net-(U2-OUT15)") (class "Default")
      (node (ref "SV2") (pin "16") (pinfunction "16_16") (pintype "passive"))
      (node (ref "U2") (pin "20") (pinfunction "OUT15_20") (pintype "output"))
    )
    (net (code "65") (name "Net-(U2-R-EXT)") (class "Default")
      (node (ref "R2") (pin "2") (pinfunction "2_2") (pintype "passive"))
      (node (ref "U2") (pin "23") (pinfunction "R-EXT_23") (pintype "input"))
    )
    (net (code "66") (name "Net-(U2-SDO)") (class "Default")
      (node (ref "U2") (pin "22") (pinfunction "SDO_22") (pintype "output"))
      (node (ref "U3") (pin "2") (pinfunction "SDI_2") (pintype "input"))
    )
    (net (code "67") (name "Net-(U3-OUT0)") (class "Default")
      (node (ref "SV3") (pin "1") (pinfunction "1_1") (pintype "passive"))
      (node (ref "U3") (pin "5") (pinfunction "OUT0_5") (pintype "output"))
    )
    (net (code "68") (name "Net-(U3-OUT1)") (class "Default")
      (node (ref "SV3") (pin "2") (pinfunction "2_2") (pintype "passive"))
      (node (ref "U3") (pin "6") (pinfunction "OUT1_6") (pintype "output"))
    )
    (net (code "69") (name "Net-(U3-OUT2)") (class "Default")
      (node (ref "SV3") (pin "3") (pinfunction "3_3") (pintype "passive"))
      (node (ref "U3") (pin "7") (pinfunction "OUT2_7") (pintype "output"))
    )
    (net (code "70") (name "Net-(U3-OUT3)") (class "Default")
      (node (ref "SV3") (pin "4") (pinfunction "4_4") (pintype "passive"))
      (node (ref "U3") (pin "8") (pinfunction "OUT3_8") (pintype "output"))
    )
    (net (code "71") (name "Net-(U3-OUT4)") (class "Default")
      (node (ref "SV3") (pin "5") (pinfunction "5_5") (pintype "passive"))
      (node (ref "U3") (pin "9") (pinfunction "OUT4_9") (pintype "output"))
    )
    (net (code "72") (name "Net-(U3-OUT5)") (class "Default")
      (node (ref "SV3") (pin "6") (pinfunction "6_6") (pintype "passive"))
      (node (ref "U3") (pin "10") (pinfunction "OUT5_10") (pintype "output"))
    )
    (net (code "73") (name "Net-(U3-OUT6)") (class "Default")
      (node (ref "SV3") (pin "7") (pinfunction "7_7") (pintype "passive"))
      (node (ref "U3") (pin "11") (pinfunction "OUT6_11") (pintype "output"))
    )
    (net (code "74") (name "Net-(U3-OUT7)") (class "Default")
      (node (ref "SV3") (pin "8") (pinfunction "8_8") (pintype "passive"))
      (node (ref "U3") (pin "12") (pinfunction "OUT7_12") (pintype "output"))
    )
    (net (code "75") (name "Net-(U3-OUT8)") (class "Default")
      (node (ref "SV3") (pin "9") (pinfunction "9_9") (pintype "passive"))
      (node (ref "U3") (pin "13") (pinfunction "OUT8_13") (pintype "output"))
    )
    (net (code "76") (name "Net-(U3-OUT9)") (class "Default")
      (node (ref "SV3") (pin "10") (pinfunction "10_10") (pintype "passive"))
      (node (ref "U3") (pin "14") (pinfunction "OUT9_14") (pintype "output"))
    )
    (net (code "77") (name "Net-(U3-OUT10)") (class "Default")
      (node (ref "SV3") (pin "11") (pinfunction "11_11") (pintype "passive"))
      (node (ref "U3") (pin "15") (pinfunction "OUT10_15") (pintype "output"))
    )
    (net (code "78") (name "Net-(U3-OUT11)") (class "Default")
      (node (ref "SV3") (pin "12") (pinfunction "12_12") (pintype "passive"))
      (node (ref "U3") (pin "16") (pinfunction "OUT11_16") (pintype "output"))
    )
    (net (code "79") (name "Net-(U3-OUT12)") (class "Default")
      (node (ref "SV3") (pin "13") (pinfunction "13_13") (pintype "passive"))
      (node (ref "U3") (pin "17") (pinfunction "OUT12_17") (pintype "output"))
    )
    (net (code "80") (name "Net-(U3-OUT13)") (class "Default")
      (node (ref "SV3") (pin "14") (pinfunction "14_14") (pintype "passive"))
      (node (ref "U3") (pin "18") (pinfunction "OUT13_18") (pintype "output"))
    )
    (net (code "81") (name "Net-(U3-OUT14)") (class "Default")
      (node (ref "SV3") (pin "15") (pinfunction "15_15") (pintype "passive"))
      (node (ref "U3") (pin "19") (pinfunction "OUT14_19") (pintype "output"))
    )
    (net (code "82") (name "Net-(U3-OUT15)") (class "Default")
      (node (ref "SV3") (pin "16") (pinfunction "16_16") (pintype "passive"))
      (node (ref "U3") (pin "20") (pinfunction "OUT15_20") (pintype "output"))
    )
    (net (code "83") (name "Net-(U3-R-EXT)") (class "Default")
      (node (ref "R3") (pin "2") (pinfunction "2_2") (pintype "passive"))
      (node (ref "U3") (pin "23") (pinfunction "R-EXT_23") (pintype "input"))
    )
    (net (code "84") (name "Net-(U3-SDO)") (class "Default")
      (node (ref "U3") (pin "22") (pinfunction "SDO_22") (pintype "output"))
      (node (ref "U4") (pin "2") (pinfunction "SDI_2") (pintype "input"))
    )
    (net (code "85") (name "Net-(U4-OUT0)") (class "Default")
      (node (ref "SV4") (pin "1") (pinfunction "1_1") (pintype "passive"))
      (node (ref "U4") (pin "5") (pinfunction "OUT0_5") (pintype "output"))
    )
    (net (code "86") (name "Net-(U4-OUT1)") (class "Default")
      (node (ref "SV4") (pin "2") (pinfunction "2_2") (pintype "passive"))
      (node (ref "U4") (pin "6") (pinfunction "OUT1_6") (pintype "output"))
    )
    (net (code "87") (name "Net-(U4-OUT2)") (class "Default")
      (node (ref "SV4") (pin "3") (pinfunction "3_3") (pintype "passive"))
      (node (ref "U4") (pin "7") (pinfunction "OUT2_7") (pintype "output"))
    )
    (net (code "88") (name "Net-(U4-OUT3)") (class "Default")
      (node (ref "SV4") (pin "4") (pinfunction "4_4") (pintype "passive"))
      (node (ref "U4") (pin "8") (pinfunction "OUT3_8") (pintype "output"))
    )
    (net (code "89") (name "Net-(U4-OUT4)") (class "Default")
      (node (ref "SV4") (pin "5") (pinfunction "5_5") (pintype "passive"))
      (node (ref "U4") (pin "9") (pinfunction "OUT4_9") (pintype "output"))
    )
    (net (code "90") (name "Net-(U4-OUT5)") (class "Default")
      (node (ref "SV4") (pin "6") (pinfunction "6_6") (pintype "passive"))
      (node (ref "U4") (pin "10") (pinfunction "OUT5_10") (pintype "output"))
    )
    (net (code "91") (name "Net-(U4-OUT6)") (class "Default")
      (node (ref "SV4") (pin "7") (pinfunction "7_7") (pintype "passive"))
      (node (ref "U4") (pin "11") (pinfunction "OUT6_11") (pintype "output"))
    )
    (net (code "92") (name "Net-(U4-OUT7)") (class "Default")
      (node (ref "SV4") (pin "8") (pinfunction "8_8") (pintype "passive"))
      (node (ref "U4") (pin "12") (pinfunction "OUT7_12") (pintype "output"))
    )
    (net (code "93") (name "Net-(U4-OUT8)") (class "Default")
      (node (ref "SV4") (pin "9") (pinfunction "9_9") (pintype "passive"))
      (node (ref "U4") (pin "13") (pinfunction "OUT8_13") (pintype "output"))
    )
    (net (code "94") (name "Net-(U4-OUT9)") (class "Default")
      (node (ref "SV4") (pin "10") (pinfunction "10_10") (pintype "passive"))
      (node (ref "U4") (pin "14") (pinfunction "OUT9_14") (pintype "output"))
    )
    (net (code "95") (name "Net-(U4-OUT10)") (class "Default")
      (node (ref "SV4") (pin "11") (pinfunction "11_11") (pintype "passive"))
      (node (ref "U4") (pin "15") (pinfunction "OUT10_15") (pintype "output"))
    )
    (net (code "96") (name "Net-(U4-OUT11)") (class "Default")
      (node (ref "SV4") (pin "12") (pinfunction "12_12") (pintype "passive"))
      (node (ref "U4") (pin "16") (pinfunction "OUT11_16") (pintype "output"))
    )
    (net (code "97") (name "Net-(U4-OUT12)") (class "Default")
      (node (ref "SV4") (pin "13") (pinfunction "13_13") (pintype "passive"))
      (node (ref "U4") (pin "17") (pinfunction "OUT12_17") (pintype "output"))
    )
    (net (code "98") (name "Net-(U4-OUT13)") (class "Default")
      (node (ref "SV4") (pin "14") (pinfunction "14_14") (pintype "passive"))
      (node (ref "U4") (pin "18") (pinfunction "OUT13_18") (pintype "output"))
    )
    (net (code "99") (name "Net-(U4-OUT14)") (class "Default")
      (node (ref "SV4") (pin "15") (pinfunction "15_15") (pintype "passive"))
      (node (ref "U4") (pin "19") (pinfunction "OUT14_19") (pintype "output"))
    )
    (net (code "100") (name "Net-(U4-OUT15)") (class "Default")
      (node (ref "SV4") (pin "16") (pinfunction "16_16") (pintype "passive"))
      (node (ref "U4") (pin "20") (pinfunction "OUT15_20") (pintype "output"))
    )
    (net (code "101") (name "Net-(U4-R-EXT)") (class "Default")
      (node (ref "R4") (pin "2") (pinfunction "2_2") (pintype "passive"))
      (node (ref "U4") (pin "23") (pinfunction "R-EXT_23") (pintype "input"))
    )
    (net (code "102") (name "Net-(U5-OUT0)") (class "Default")
      (node (ref "SV5") (pin "1") (pinfunction "1_1") (pintype "passive"))
      (node (ref "U5") (pin "5") (pinfunction "OUT0_5") (pintype "output"))
    )
    (net (code "103") (name "Net-(U5-OUT1)") (class "Default")
      (node (ref "SV5") (pin "2") (pinfunction "2_2") (pintype "passive"))
      (node (ref "U5") (pin "6") (pinfunction "OUT1_6") (pintype "output"))
    )
    (net (code "104") (name "Net-(U5-OUT2)") (class "Default")
      (node (ref "SV5") (pin "3") (pinfunction "3_3") (pintype "passive"))
      (node (ref "U5") (pin "7") (pinfunction "OUT2_7") (pintype "output"))
    )
    (net (code "105") (name "Net-(U5-OUT3)") (class "Default")
      (node (ref "SV5") (pin "4") (pinfunction "4_4") (pintype "passive"))
      (node (ref "U5") (pin "8") (pinfunction "OUT3_8") (pintype "output"))
    )
    (net (code "106") (name "Net-(U5-OUT4)") (class "Default")
      (node (ref "SV5") (pin "5") (pinfunction "5_5") (pintype "passive"))
      (node (ref "U5") (pin "9") (pinfunction "OUT4_9") (pintype "output"))
    )
    (net (code "107") (name "Net-(U5-OUT5)") (class "Default")
      (node (ref "SV5") (pin "6") (pinfunction "6_6") (pintype "passive"))
      (node (ref "U5") (pin "10") (pinfunction "OUT5_10") (pintype "output"))
    )
    (net (code "108") (name "Net-(U5-OUT6)") (class "Default")
      (node (ref "SV5") (pin "7") (pinfunction "7_7") (pintype "passive"))
      (node (ref "U5") (pin "11") (pinfunction "OUT6_11") (pintype "output"))
    )
    (net (code "109") (name "Net-(U5-OUT7)") (class "Default")
      (node (ref "SV5") (pin "8") (pinfunction "8_8") (pintype "passive"))
      (node (ref "U5") (pin "12") (pinfunction "OUT7_12") (pintype "output"))
    )
    (net (code "110") (name "Net-(U5-OUT8)") (class "Default")
      (node (ref "SV5") (pin "9") (pinfunction "9_9") (pintype "passive"))
      (node (ref "U5") (pin "13") (pinfunction "OUT8_13") (pintype "output"))
    )
    (net (code "111") (name "Net-(U5-OUT9)") (class "Default")
      (node (ref "SV5") (pin "10") (pinfunction "10_10") (pintype "passive"))
      (node (ref "U5") (pin "14") (pinfunction "OUT9_14") (pintype "output"))
    )
    (net (code "112") (name "Net-(U5-OUT10)") (class "Default")
      (node (ref "SV5") (pin "11") (pinfunction "11_11") (pintype "passive"))
      (node (ref "U5") (pin "15") (pinfunction "OUT10_15") (pintype "output"))
    )
    (net (code "113") (name "Net-(U5-OUT11)") (class "Default")
      (node (ref "SV5") (pin "12") (pinfunction "12_12") (pintype "passive"))
      (node (ref "U5") (pin "16") (pinfunction "OUT11_16") (pintype "output"))
    )
    (net (code "114") (name "Net-(U5-OUT12)") (class "Default")
      (node (ref "SV5") (pin "13") (pinfunction "13_13") (pintype "passive"))
      (node (ref "U5") (pin "17") (pinfunction "OUT12_17") (pintype "output"))
    )
    (net (code "115") (name "Net-(U5-OUT13)") (class "Default")
      (node (ref "SV5") (pin "14") (pinfunction "14_14") (pintype "passive"))
      (node (ref "U5") (pin "18") (pinfunction "OUT13_18") (pintype "output"))
    )
    (net (code "116") (name "Net-(U5-OUT14)") (class "Default")
      (node (ref "SV5") (pin "15") (pinfunction "15_15") (pintype "passive"))
      (node (ref "U5") (pin "19") (pinfunction "OUT14_19") (pintype "output"))
    )
    (net (code "117") (name "Net-(U5-OUT15)") (class "Default")
      (node (ref "SV5") (pin "16") (pinfunction "16_16") (pintype "passive"))
      (node (ref "U5") (pin "20") (pinfunction "OUT15_20") (pintype "output"))
    )
    (net (code "118") (name "Net-(U5-R-EXT)") (class "Default")
      (node (ref "R5") (pin "2") (pinfunction "2_2") (pintype "passive"))
      (node (ref "U5") (pin "23") (pinfunction "R-EXT_23") (pintype "input"))
    )
    (net (code "119") (name "Net-(U5-SDO)") (class "Default")
      (node (ref "U5") (pin "22") (pinfunction "SDO_22") (pintype "output"))
      (node (ref "U6") (pin "2") (pinfunction "SDI_2") (pintype "input"))
    )
    (net (code "120") (name "Net-(U6-OUT0)") (class "Default")
      (node (ref "SV6") (pin "1") (pinfunction "1_1") (pintype "passive"))
      (node (ref "U6") (pin "5") (pinfunction "OUT0_5") (pintype "output"))
    )
    (net (code "121") (name "Net-(U6-OUT1)") (class "Default")
      (node (ref "SV6") (pin "2") (pinfunction "2_2") (pintype "passive"))
      (node (ref "U6") (pin "6") (pinfunction "OUT1_6") (pintype "output"))
    )
    (net (code "122") (name "Net-(U6-OUT2)") (class "Default")
      (node (ref "SV6") (pin "3") (pinfunction "3_3") (pintype "passive"))
      (node (ref "U6") (pin "7") (pinfunction "OUT2_7") (pintype "output"))
    )
    (net (code "123") (name "Net-(U6-OUT3)") (class "Default")
      (node (ref "SV6") (pin "4") (pinfunction "4_4") (pintype "passive"))
      (node (ref "U6") (pin "8") (pinfunction "OUT3_8") (pintype "output"))
    )
    (net (code "124") (name "Net-(U6-OUT4)") (class "Default")
      (node (ref "SV6") (pin "5") (pinfunction "5_5") (pintype "passive"))
      (node (ref "U6") (pin "9") (pinfunction "OUT4_9") (pintype "output"))
    )
    (net (code "125") (name "Net-(U6-OUT5)") (class "Default")
      (node (ref "SV6") (pin "6") (pinfunction "6_6") (pintype "passive"))
      (node (ref "U6") (pin "10") (pinfunction "OUT5_10") (pintype "output"))
    )
    (net (code "126") (name "Net-(U6-OUT6)") (class "Default")
      (node (ref "SV6") (pin "7") (pinfunction "7_7") (pintype "passive"))
      (node (ref "U6") (pin "11") (pinfunction "OUT6_11") (pintype "output"))
    )
    (net (code "127") (name "Net-(U6-OUT7)") (class "Default")
      (node (ref "SV6") (pin "8") (pinfunction "8_8") (pintype "passive"))
      (node (ref "U6") (pin "12") (pinfunction "OUT7_12") (pintype "output"))
    )
    (net (code "128") (name "Net-(U6-OUT8)") (class "Default")
      (node (ref "SV6") (pin "9") (pinfunction "9_9") (pintype "passive"))
      (node (ref "U6") (pin "13") (pinfunction "OUT8_13") (pintype "output"))
    )
    (net (code "129") (name "Net-(U6-OUT9)") (class "Default")
      (node (ref "SV6") (pin "10") (pinfunction "10_10") (pintype "passive"))
      (node (ref "U6") (pin "14") (pinfunction "OUT9_14") (pintype "output"))
    )
    (net (code "130") (name "Net-(U6-OUT10)") (class "Default")
      (node (ref "SV6") (pin "11") (pinfunction "11_11") (pintype "passive"))
      (node (ref "U6") (pin "15") (pinfunction "OUT10_15") (pintype "output"))
    )
    (net (code "131") (name "Net-(U6-OUT11)") (class "Default")
      (node (ref "SV6") (pin "12") (pinfunction "12_12") (pintype "passive"))
      (node (ref "U6") (pin "16") (pinfunction "OUT11_16") (pintype "output"))
    )
    (net (code "132") (name "Net-(U6-OUT12)") (class "Default")
      (node (ref "SV6") (pin "13") (pinfunction "13_13") (pintype "passive"))
      (node (ref "U6") (pin "17") (pinfunction "OUT12_17") (pintype "output"))
    )
    (net (code "133") (name "Net-(U6-OUT13)") (class "Default")
      (node (ref "SV6") (pin "14") (pinfunction "14_14") (pintype "passive"))
      (node (ref "U6") (pin "18") (pinfunction "OUT13_18") (pintype "output"))
    )
    (net (code "134") (name "Net-(U6-OUT14)") (class "Default")
      (node (ref "SV6") (pin "15") (pinfunction "15_15") (pintype "passive"))
      (node (ref "U6") (pin "19") (pinfunction "OUT14_19") (pintype "output"))
    )
    (net (code "135") (name "Net-(U6-OUT15)") (class "Default")
      (node (ref "SV6") (pin "16") (pinfunction "16_16") (pintype "passive"))
      (node (ref "U6") (pin "20") (pinfunction "OUT15_20") (pintype "output"))
    )
    (net (code "136") (name "Net-(U6-R-EXT)") (class "Default")
      (node (ref "R6") (pin "2") (pinfunction "2_2") (pintype "passive"))
      (node (ref "U6") (pin "23") (pinfunction "R-EXT_23") (pintype "input"))
    )
    (net (code "137") (name "Net-(U6-SDO)") (class "Default")
      (node (ref "U6") (pin "22") (pinfunction "SDO_22") (pintype "output"))
      (node (ref "U7") (pin "2") (pinfunction "SDI_2") (pintype "input"))
    )
    (net (code "138") (name "Net-(U7-OUT0)") (class "Default")
      (node (ref "SV7") (pin "1") (pinfunction "1_1") (pintype "passive"))
      (node (ref "U7") (pin "5") (pinfunction "OUT0_5") (pintype "output"))
    )
    (net (code "139") (name "Net-(U7-OUT1)") (class "Default")
      (node (ref "SV7") (pin "2") (pinfunction "2_2") (pintype "passive"))
      (node (ref "U7") (pin "6") (pinfunction "OUT1_6") (pintype "output"))
    )
    (net (code "140") (name "Net-(U7-OUT2)") (class "Default")
      (node (ref "SV7") (pin "3") (pinfunction "3_3") (pintype "passive"))
      (node (ref "U7") (pin "7") (pinfunction "OUT2_7") (pintype "output"))
    )
    (net (code "141") (name "Net-(U7-OUT3)") (class "Default")
      (node (ref "SV7") (pin "4") (pinfunction "4_4") (pintype "passive"))
      (node (ref "U7") (pin "8") (pinfunction "OUT3_8") (pintype "output"))
    )
    (net (code "142") (name "Net-(U7-OUT4)") (class "Default")
      (node (ref "SV7") (pin "5") (pinfunction "5_5") (pintype "passive"))
      (node (ref "U7") (pin "9") (pinfunction "OUT4_9") (pintype "output"))
    )
    (net (code "143") (name "Net-(U7-OUT5)") (class "Default")
      (node (ref "SV7") (pin "6") (pinfunction "6_6") (pintype "passive"))
      (node (ref "U7") (pin "10") (pinfunction "OUT5_10") (pintype "output"))
    )
    (net (code "144") (name "Net-(U7-OUT6)") (class "Default")
      (node (ref "SV7") (pin "7") (pinfunction "7_7") (pintype "passive"))
      (node (ref "U7") (pin "11") (pinfunction "OUT6_11") (pintype "output"))
    )
    (net (code "145") (name "Net-(U7-OUT7)") (class "Default")
      (node (ref "SV7") (pin "8") (pinfunction "8_8") (pintype "passive"))
      (node (ref "U7") (pin "12") (pinfunction "OUT7_12") (pintype "output"))
    )
    (net (code "146") (name "Net-(U7-OUT8)") (class "Default")
      (node (ref "SV7") (pin "9") (pinfunction "9_9") (pintype "passive"))
      (node (ref "U7") (pin "13") (pinfunction "OUT8_13") (pintype "output"))
    )
    (net (code "147") (name "Net-(U7-OUT9)") (class "Default")
      (node (ref "SV7") (pin "10") (pinfunction "10_10") (pintype "passive"))
      (node (ref "U7") (pin "14") (pinfunction "OUT9_14") (pintype "output"))
    )
    (net (code "148") (name "Net-(U7-OUT10)") (class "Default")
      (node (ref "SV7") (pin "11") (pinfunction "11_11") (pintype "passive"))
      (node (ref "U7") (pin "15") (pinfunction "OUT10_15") (pintype "output"))
    )
    (net (code "149") (name "Net-(U7-OUT11)") (class "Default")
      (node (ref "SV7") (pin "12") (pinfunction "12_12") (pintype "passive"))
      (node (ref "U7") (pin "16") (pinfunction "OUT11_16") (pintype "output"))
    )
    (net (code "150") (name "Net-(U7-OUT12)") (class "Default")
      (node (ref "SV7") (pin "13") (pinfunction "13_13") (pintype "passive"))
      (node (ref "U7") (pin "17") (pinfunction "OUT12_17") (pintype "output"))
    )
    (net (code "151") (name "Net-(U7-OUT13)") (class "Default")
      (node (ref "SV7") (pin "14") (pinfunction "14_14") (pintype "passive"))
      (node (ref "U7") (pin "18") (pinfunction "OUT13_18") (pintype "output"))
    )
    (net (code "152") (name "Net-(U7-OUT14)") (class "Default")
      (node (ref "SV7") (pin "15") (pinfunction "15_15") (pintype "passive"))
      (node (ref "U7") (pin "19") (pinfunction "OUT14_19") (pintype "output"))
    )
    (net (code "153") (name "Net-(U7-OUT15)") (class "Default")
      (node (ref "SV7") (pin "16") (pinfunction "16_16") (pintype "passive"))
      (node (ref "U7") (pin "20") (pinfunction "OUT15_20") (pintype "output"))
    )
    (net (code "154") (name "Net-(U7-R-EXT)") (class "Default")
      (node (ref "R7") (pin "2") (pinfunction "2_2") (pintype "passive"))
      (node (ref "U7") (pin "23") (pinfunction "R-EXT_23") (pintype "input"))
    )
    (net (code "155") (name "Net-(U7-SDO)") (class "Default")
      (node (ref "U7") (pin "22") (pinfunction "SDO_22") (pintype "output"))
      (node (ref "U8") (pin "2") (pinfunction "SDI_2") (pintype "input"))
    )
    (net (code "156") (name "Net-(U8-OUT0)") (class "Default")
      (node (ref "SV8") (pin "1") (pinfunction "1_1") (pintype "passive"))
      (node (ref "U8") (pin "5") (pinfunction "OUT0_5") (pintype "output"))
    )
    (net (code "157") (name "Net-(U8-OUT1)") (class "Default")
      (node (ref "SV8") (pin "2") (pinfunction "2_2") (pintype "passive"))
      (node (ref "U8") (pin "6") (pinfunction "OUT1_6") (pintype "output"))
    )
    (net (code "158") (name "Net-(U8-OUT2)") (class "Default")
      (node (ref "SV8") (pin "3") (pinfunction "3_3") (pintype "passive"))
      (node (ref "U8") (pin "7") (pinfunction "OUT2_7") (pintype "output"))
    )
    (net (code "159") (name "Net-(U8-OUT3)") (class "Default")
      (node (ref "SV8") (pin "4") (pinfunction "4_4") (pintype "passive"))
      (node (ref "U8") (pin "8") (pinfunction "OUT3_8") (pintype "output"))
    )
    (net (code "160") (name "Net-(U8-OUT4)") (class "Default")
      (node (ref "SV8") (pin "5") (pinfunction "5_5") (pintype "passive"))
      (node (ref "U8") (pin "9") (pinfunction "OUT4_9") (pintype "output"))
    )
    (net (code "161") (name "Net-(U8-OUT5)") (class "Default")
      (node (ref "SV8") (pin "6") (pinfunction "6_6") (pintype "passive"))
      (node (ref "U8") (pin "10") (pinfunction "OUT5_10") (pintype "output"))
    )
    (net (code "162") (name "Net-(U8-OUT6)") (class "Default")
      (node (ref "SV8") (pin "7") (pinfunction "7_7") (pintype "passive"))
      (node (ref "U8") (pin "11") (pinfunction "OUT6_11") (pintype "output"))
    )
    (net (code "163") (name "Net-(U8-OUT7)") (class "Default")
      (node (ref "SV8") (pin "8") (pinfunction "8_8") (pintype "passive"))
      (node (ref "U8") (pin "12") (pinfunction "OUT7_12") (pintype "output"))
    )
    (net (code "164") (name "Net-(U8-OUT8)") (class "Default")
      (node (ref "SV8") (pin "9") (pinfunction "9_9") (pintype "passive"))
      (node (ref "U8") (pin "13") (pinfunction "OUT8_13") (pintype "output"))
    )
    (net (code "165") (name "Net-(U8-OUT9)") (class "Default")
      (node (ref "SV8") (pin "10") (pinfunction "10_10") (pintype "passive"))
      (node (ref "U8") (pin "14") (pinfunction "OUT9_14") (pintype "output"))
    )
    (net (code "166") (name "Net-(U8-OUT10)") (class "Default")
      (node (ref "SV8") (pin "11") (pinfunction "11_11") (pintype "passive"))
      (node (ref "U8") (pin "15") (pinfunction "OUT10_15") (pintype "output"))
    )
    (net (code "167") (name "Net-(U8-OUT11)") (class "Default")
      (node (ref "SV8") (pin "12") (pinfunction "12_12") (pintype "passive"))
      (node (ref "U8") (pin "16") (pinfunction "OUT11_16") (pintype "output"))
    )
    (net (code "168") (name "Net-(U8-OUT12)") (class "Default")
      (node (ref "SV8") (pin "13") (pinfunction "13_13") (pintype "passive"))
      (node (ref "U8") (pin "17") (pinfunction "OUT12_17") (pintype "output"))
    )
    (net (code "169") (name "Net-(U8-OUT13)") (class "Default")
      (node (ref "SV8") (pin "14") (pinfunction "14_14") (pintype "passive"))
      (node (ref "U8") (pin "18") (pinfunction "OUT13_18") (pintype "output"))
    )
    (net (code "170") (name "Net-(U8-OUT14)") (class "Default")
      (node (ref "SV8") (pin "15") (pinfunction "15_15") (pintype "passive"))
      (node (ref "U8") (pin "19") (pinfunction "OUT14_19") (pintype "output"))
    )
    (net (code "171") (name "Net-(U8-OUT15)") (class "Default")
      (node (ref "SV8") (pin "16") (pinfunction "16_16") (pintype "passive"))
      (node (ref "U8") (pin "20") (pinfunction "OUT15_20") (pintype "output"))
    )
    (net (code "172") (name "Net-(U8-R-EXT)") (class "Default")
      (node (ref "R8") (pin "2") (pinfunction "2_2") (pintype "passive"))
      (node (ref "U8") (pin "23") (pinfunction "R-EXT_23") (pintype "input"))
    )
    (net (code "173") (name "Net-(U9-OUT0)") (class "Default")
      (node (ref "SV9") (pin "1") (pinfunction "1_1") (pintype "passive"))
      (node (ref "U9") (pin "5") (pinfunction "OUT0_5") (pintype "output"))
    )
    (net (code "174") (name "Net-(U9-OUT1)") (class "Default")
      (node (ref "SV9") (pin "2") (pinfunction "2_2") (pintype "passive"))
      (node (ref "U9") (pin "6") (pinfunction "OUT1_6") (pintype "output"))
    )
    (net (code "175") (name "Net-(U9-OUT2)") (class "Default")
      (node (ref "SV9") (pin "3") (pinfunction "3_3") (pintype "passive"))
      (node (ref "U9") (pin "7") (pinfunction "OUT2_7") (pintype "output"))
    )
    (net (code "176") (name "Net-(U9-OUT3)") (class "Default")
      (node (ref "SV9") (pin "4") (pinfunction "4_4") (pintype "passive"))
      (node (ref "U9") (pin "8") (pinfunction "OUT3_8") (pintype "output"))
    )
    (net (code "177") (name "Net-(U9-OUT4)") (class "Default")
      (node (ref "SV9") (pin "5") (pinfunction "5_5") (pintype "passive"))
      (node (ref "U9") (pin "9") (pinfunction "OUT4_9") (pintype "output"))
    )
    (net (code "178") (name "Net-(U9-OUT5)") (class "Default")
      (node (ref "SV9") (pin "6") (pinfunction "6_6") (pintype "passive"))
      (node (ref "U9") (pin "10") (pinfunction "OUT5_10") (pintype "output"))
    )
    (net (code "179") (name "Net-(U9-OUT6)") (class "Default")
      (node (ref "SV9") (pin "7") (pinfunction "7_7") (pintype "passive"))
      (node (ref "U9") (pin "11") (pinfunction "OUT6_11") (pintype "output"))
    )
    (net (code "180") (name "Net-(U9-OUT7)") (class "Default")
      (node (ref "SV9") (pin "8") (pinfunction "8_8") (pintype "passive"))
      (node (ref "U9") (pin "12") (pinfunction "OUT7_12") (pintype "output"))
    )
    (net (code "181") (name "Net-(U9-OUT8)") (class "Default")
      (node (ref "SV9") (pin "9") (pinfunction "9_9") (pintype "passive"))
      (node (ref "U9") (pin "13") (pinfunction "OUT8_13") (pintype "output"))
    )
    (net (code "182") (name "Net-(U9-OUT9)") (class "Default")
      (node (ref "SV9") (pin "10") (pinfunction "10_10") (pintype "passive"))
      (node (ref "U9") (pin "14") (pinfunction "OUT9_14") (pintype "output"))
    )
    (net (code "183") (name "Net-(U9-OUT10)") (class "Default")
      (node (ref "SV9") (pin "11") (pinfunction "11_11") (pintype "passive"))
      (node (ref "U9") (pin "15") (pinfunction "OUT10_15") (pintype "output"))
    )
    (net (code "184") (name "Net-(U9-OUT11)") (class "Default")
      (node (ref "SV9") (pin "12") (pinfunction "12_12") (pintype "passive"))
      (node (ref "U9") (pin "16") (pinfunction "OUT11_16") (pintype "output"))
    )
    (net (code "185") (name "Net-(U9-OUT12)") (class "Default")
      (node (ref "SV9") (pin "13") (pinfunction "13_13") (pintype "passive"))
      (node (ref "U9") (pin "17") (pinfunction "OUT12_17") (pintype "output"))
    )
    (net (code "186") (name "Net-(U9-OUT13)") (class "Default")
      (node (ref "SV9") (pin "14") (pinfunction "14_14") (pintype "passive"))
      (node (ref "U9") (pin "18") (pinfunction "OUT13_18") (pintype "output"))
    )
    (net (code "187") (name "Net-(U9-OUT14)") (class "Default")
      (node (ref "SV9") (pin "15") (pinfunction "15_15") (pintype "passive"))
      (node (ref "U9") (pin "19") (pinfunction "OUT14_19") (pintype "output"))
    )
    (net (code "188") (name "Net-(U9-OUT15)") (class "Default")
      (node (ref "SV9") (pin "16") (pinfunction "16_16") (pintype "passive"))
      (node (ref "U9") (pin "20") (pinfunction "OUT15_20") (pintype "output"))
    )
    (net (code "189") (name "Net-(U9-R-EXT)") (class "Default")
      (node (ref "R9") (pin "2") (pinfunction "2_2") (pintype "passive"))
      (node (ref "U9") (pin "23") (pinfunction "R-EXT_23") (pintype "input"))
    )
    (net (code "190") (name "Net-(U10-OUT0)") (class "Default")
      (node (ref "SV10") (pin "1") (pinfunction "1_1") (pintype "passive"))
      (node (ref "U10") (pin "5") (pinfunction "OUT0_5") (pintype "output"))
    )
    (net (code "191") (name "Net-(U10-OUT1)") (class "Default")
      (node (ref "SV10") (pin "2") (pinfunction "2_2") (pintype "passive"))
      (node (ref "U10") (pin "6") (pinfunction "OUT1_6") (pintype "output"))
    )
    (net (code "192") (name "Net-(U10-OUT2)") (class "Default")
      (node (ref "SV10") (pin "3") (pinfunction "3_3") (pintype "passive"))
      (node (ref "U10") (pin "7") (pinfunction "OUT2_7") (pintype "output"))
    )
    (net (code "193") (name "Net-(U10-OUT3)") (class "Default")
      (node (ref "SV10") (pin "4") (pinfunction "4_4") (pintype "passive"))
      (node (ref "U10") (pin "8") (pinfunction "OUT3_8") (pintype "output"))
    )
    (net (code "194") (name "Net-(U10-OUT4)") (class "Default")
      (node (ref "SV10") (pin "5") (pinfunction "5_5") (pintype "passive"))
      (node (ref "U10") (pin "9") (pinfunction "OUT4_9") (pintype "output"))
    )
    (net (code "195") (name "Net-(U10-OUT5)") (class "Default")
      (node (ref "SV10") (pin "6") (pinfunction "6_6") (pintype "passive"))
      (node (ref "U10") (pin "10") (pinfunction "OUT5_10") (pintype "output"))
    )
    (net (code "196") (name "Net-(U10-OUT6)") (class "Default")
      (node (ref "SV10") (pin "7") (pinfunction "7_7") (pintype "passive"))
      (node (ref "U10") (pin "11") (pinfunction "OUT6_11") (pintype "output"))
    )
    (net (code "197") (name "Net-(U10-OUT7)") (class "Default")
      (node (ref "SV10") (pin "8") (pinfunction "8_8") (pintype "passive"))
      (node (ref "U10") (pin "12") (pinfunction "OUT7_12") (pintype "output"))
    )
    (net (code "198") (name "Net-(U10-OUT8)") (class "Default")
      (node (ref "SV10") (pin "9") (pinfunction "9_9") (pintype "passive"))
      (node (ref "U10") (pin "13") (pinfunction "OUT8_13") (pintype "output"))
    )
    (net (code "199") (name "Net-(U10-OUT9)") (class "Default")
      (node (ref "SV10") (pin "10") (pinfunction "10_10") (pintype "passive"))
      (node (ref "U10") (pin "14") (pinfunction "OUT9_14") (pintype "output"))
    )
    (net (code "200") (name "Net-(U10-OUT10)") (class "Default")
      (node (ref "SV10") (pin "11") (pinfunction "11_11") (pintype "passive"))
      (node (ref "U10") (pin "15") (pinfunction "OUT10_15") (pintype "output"))
    )
    (net (code "201") (name "Net-(U10-OUT11)") (class "Default")
      (node (ref "SV10") (pin "12") (pinfunction "12_12") (pintype "passive"))
      (node (ref "U10") (pin "16") (pinfunction "OUT11_16") (pintype "output"))
    )
    (net (code "202") (name "Net-(U10-OUT12)") (class "Default")
      (node (ref "SV10") (pin "13") (pinfunction "13_13") (pintype "passive"))
      (node (ref "U10") (pin "17") (pinfunction "OUT12_17") (pintype "output"))
    )
    (net (code "203") (name "Net-(U10-OUT13)") (class "Default")
      (node (ref "SV10") (pin "14") (pinfunction "14_14") (pintype "passive"))
      (node (ref "U10") (pin "18") (pinfunction "OUT13_18") (pintype "output"))
    )
    (net (code "204") (name "Net-(U10-OUT14)") (class "Default")
      (node (ref "SV10") (pin "15") (pinfunction "15_15") (pintype "passive"))
      (node (ref "U10") (pin "19") (pinfunction "OUT14_19") (pintype "output"))
    )
    (net (code "205") (name "Net-(U10-OUT15)") (class "Default")
      (node (ref "SV10") (pin "16") (pinfunction "16_16") (pintype "passive"))
      (node (ref "U10") (pin "20") (pinfunction "OUT15_20") (pintype "output"))
    )
    (net (code "206") (name "Net-(U10-R-EXT)") (class "Default")
      (node (ref "R10") (pin "2") (pinfunction "2_2") (pintype "passive"))
      (node (ref "U10") (pin "23") (pinfunction "R-EXT_23") (pintype "input"))
    )
    (net (code "207") (name "Net-(U10-SDI)") (class "Default")
      (node (ref "U10") (pin "2") (pinfunction "SDI_2") (pintype "input"))
      (node (ref "U9") (pin "22") (pinfunction "SDO_22") (pintype "output"))
    )
    (net (code "208") (name "Net-(U10-SDO)") (class "Default")
      (node (ref "U10") (pin "22") (pinfunction "SDO_22") (pintype "output"))
      (node (ref "U11") (pin "2") (pinfunction "SDI_2") (pintype "input"))
    )
    (net (code "209") (name "Net-(U11-OUT0)") (class "Default")
      (node (ref "SV11") (pin "1") (pinfunction "1_1") (pintype "passive"))
      (node (ref "U11") (pin "5") (pinfunction "OUT0_5") (pintype "output"))
    )
    (net (code "210") (name "Net-(U11-OUT1)") (class "Default")
      (node (ref "SV11") (pin "2") (pinfunction "2_2") (pintype "passive"))
      (node (ref "U11") (pin "6") (pinfunction "OUT1_6") (pintype "output"))
    )
    (net (code "211") (name "Net-(U11-OUT2)") (class "Default")
      (node (ref "SV11") (pin "3") (pinfunction "3_3") (pintype "passive"))
      (node (ref "U11") (pin "7") (pinfunction "OUT2_7") (pintype "output"))
    )
    (net (code "212") (name "Net-(U11-OUT3)") (class "Default")
      (node (ref "SV11") (pin "4") (pinfunction "4_4") (pintype "passive"))
      (node (ref "U11") (pin "8") (pinfunction "OUT3_8") (pintype "output"))
    )
    (net (code "213") (name "Net-(U11-OUT4)") (class "Default")
      (node (ref "SV11") (pin "5") (pinfunction "5_5") (pintype "passive"))
      (node (ref "U11") (pin "9") (pinfunction "OUT4_9") (pintype "output"))
    )
    (net (code "214") (name "Net-(U11-OUT5)") (class "Default")
      (node (ref "SV11") (pin "6") (pinfunction "6_6") (pintype "passive"))
      (node (ref "U11") (pin "10") (pinfunction "OUT5_10") (pintype "output"))
    )
    (net (code "215") (name "Net-(U11-OUT6)") (class "Default")
      (node (ref "SV11") (pin "7") (pinfunction "7_7") (pintype "passive"))
      (node (ref "U11") (pin "11") (pinfunction "OUT6_11") (pintype "output"))
    )
    (net (code "216") (name "Net-(U11-OUT7)") (class "Default")
      (node (ref "SV11") (pin "8") (pinfunction "8_8") (pintype "passive"))
      (node (ref "U11") (pin "12") (pinfunction "OUT7_12") (pintype "output"))
    )
    (net (code "217") (name "Net-(U11-OUT8)") (class "Default")
      (node (ref "SV11") (pin "9") (pinfunction "9_9") (pintype "passive"))
      (node (ref "U11") (pin "13") (pinfunction "OUT8_13") (pintype "output"))
    )
    (net (code "218") (name "Net-(U11-OUT9)") (class "Default")
      (node (ref "SV11") (pin "10") (pinfunction "10_10") (pintype "passive"))
      (node (ref "U11") (pin "14") (pinfunction "OUT9_14") (pintype "output"))
    )
    (net (code "219") (name "Net-(U11-OUT10)") (class "Default")
      (node (ref "SV11") (pin "11") (pinfunction "11_11") (pintype "passive"))
      (node (ref "U11") (pin "15") (pinfunction "OUT10_15") (pintype "output"))
    )
    (net (code "220") (name "Net-(U11-OUT11)") (class "Default")
      (node (ref "SV11") (pin "12") (pinfunction "12_12") (pintype "passive"))
      (node (ref "U11") (pin "16") (pinfunction "OUT11_16") (pintype "output"))
    )
    (net (code "221") (name "Net-(U11-OUT12)") (class "Default")
      (node (ref "SV11") (pin "13") (pinfunction "13_13") (pintype "passive"))
      (node (ref "U11") (pin "17") (pinfunction "OUT12_17") (pintype "output"))
    )
    (net (code "222") (name "Net-(U11-OUT13)") (class "Default")
      (node (ref "SV11") (pin "14") (pinfunction "14_14") (pintype "passive"))
      (node (ref "U11") (pin "18") (pinfunction "OUT13_18") (pintype "output"))
    )
    (net (code "223") (name "Net-(U11-OUT14)") (class "Default")
      (node (ref "SV11") (pin "15") (pinfunction "15_15") (pintype "passive"))
      (node (ref "U11") (pin "19") (pinfunction "OUT14_19") (pintype "output"))
    )
    (net (code "224") (name "Net-(U11-OUT15)") (class "Default")
      (node (ref "SV11") (pin "16") (pinfunction "16_16") (pintype "passive"))
      (node (ref "U11") (pin "20") (pinfunction "OUT15_20") (pintype "output"))
    )
    (net (code "225") (name "Net-(U11-R-EXT)") (class "Default")
      (node (ref "R11") (pin "2") (pinfunction "2_2") (pintype "passive"))
      (node (ref "U11") (pin "23") (pinfunction "R-EXT_23") (pintype "input"))
    )
    (net (code "226") (name "Net-(U11-SDO)") (class "Default")
      (node (ref "U11") (pin "22") (pinfunction "SDO_22") (pintype "output"))
      (node (ref "U12") (pin "2") (pinfunction "SDI_2") (pintype "input"))
    )
    (net (code "227") (name "Net-(U12-OUT0)") (class "Default")
      (node (ref "SV12") (pin "1") (pinfunction "1_1") (pintype "passive"))
      (node (ref "U12") (pin "5") (pinfunction "OUT0_5") (pintype "output"))
    )
    (net (code "228") (name "Net-(U12-OUT1)") (class "Default")
      (node (ref "SV12") (pin "2") (pinfunction "2_2") (pintype "passive"))
      (node (ref "U12") (pin "6") (pinfunction "OUT1_6") (pintype "output"))
    )
    (net (code "229") (name "Net-(U12-OUT2)") (class "Default")
      (node (ref "SV12") (pin "3") (pinfunction "3_3") (pintype "passive"))
      (node (ref "U12") (pin "7") (pinfunction "OUT2_7") (pintype "output"))
    )
    (net (code "230") (name "Net-(U12-OUT3)") (class "Default")
      (node (ref "SV12") (pin "4") (pinfunction "4_4") (pintype "passive"))
      (node (ref "U12") (pin "8") (pinfunction "OUT3_8") (pintype "output"))
    )
    (net (code "231") (name "Net-(U12-OUT4)") (class "Default")
      (node (ref "SV12") (pin "5") (pinfunction "5_5") (pintype "passive"))
      (node (ref "U12") (pin "9") (pinfunction "OUT4_9") (pintype "output"))
    )
    (net (code "232") (name "Net-(U12-OUT5)") (class "Default")
      (node (ref "SV12") (pin "6") (pinfunction "6_6") (pintype "passive"))
      (node (ref "U12") (pin "10") (pinfunction "OUT5_10") (pintype "output"))
    )
    (net (code "233") (name "Net-(U12-OUT6)") (class "Default")
      (node (ref "SV12") (pin "7") (pinfunction "7_7") (pintype "passive"))
      (node (ref "U12") (pin "11") (pinfunction "OUT6_11") (pintype "output"))
    )
    (net (code "234") (name "Net-(U12-OUT7)") (class "Default")
      (node (ref "SV12") (pin "8") (pinfunction "8_8") (pintype "passive"))
      (node (ref "U12") (pin "12") (pinfunction "OUT7_12") (pintype "output"))
    )
    (net (code "235") (name "Net-(U12-OUT8)") (class "Default")
      (node (ref "SV12") (pin "9") (pinfunction "9_9") (pintype "passive"))
      (node (ref "U12") (pin "13") (pinfunction "OUT8_13") (pintype "output"))
    )
    (net (code "236") (name "Net-(U12-OUT9)") (class "Default")
      (node (ref "SV12") (pin "10") (pinfunction "10_10") (pintype "passive"))
      (node (ref "U12") (pin "14") (pinfunction "OUT9_14") (pintype "output"))
    )
    (net (code "237") (name "Net-(U12-OUT10)") (class "Default")
      (node (ref "SV12") (pin "11") (pinfunction "11_11") (pintype "passive"))
      (node (ref "U12") (pin "15") (pinfunction "OUT10_15") (pintype "output"))
    )
    (net (code "238") (name "Net-(U12-OUT11)") (class "Default")
      (node (ref "SV12") (pin "12") (pinfunction "12_12") (pintype "passive"))
      (node (ref "U12") (pin "16") (pinfunction "OUT11_16") (pintype "output"))
    )
    (net (code "239") (name "Net-(U12-OUT12)") (class "Default")
      (node (ref "SV12") (pin "13") (pinfunction "13_13") (pintype "passive"))
      (node (ref "U12") (pin "17") (pinfunction "OUT12_17") (pintype "output"))
    )
    (net (code "240") (name "Net-(U12-OUT13)") (class "Default")
      (node (ref "SV12") (pin "14") (pinfunction "14_14") (pintype "passive"))
      (node (ref "U12") (pin "18") (pinfunction "OUT13_18") (pintype "output"))
    )
    (net (code "241") (name "Net-(U12-OUT14)") (class "Default")
      (node (ref "SV12") (pin "15") (pinfunction "15_15") (pintype "passive"))
      (node (ref "U12") (pin "19") (pinfunction "OUT14_19") (pintype "output"))
    )
    (net (code "242") (name "Net-(U12-OUT15)") (class "Default")
      (node (ref "SV12") (pin "16") (pinfunction "16_16") (pintype "passive"))
      (node (ref "U12") (pin "20") (pinfunction "OUT15_20") (pintype "output"))
    )
    (net (code "243") (name "Net-(U12-R-EXT)") (class "Default")
      (node (ref "R12") (pin "2") (pinfunction "2_2") (pintype "passive"))
      (node (ref "U12") (pin "23") (pinfunction "R-EXT_23") (pintype "input"))
    )
    (net (code "244") (name "SDI_B") (class "Default")
      (node (ref "SV14") (pin "12") (pinfunction "12_12") (pintype "passive"))
      (node (ref "U9") (pin "2") (pinfunction "SDI_2") (pintype "input"))
    )
    (net (code "245") (name "SDI_G") (class "Default")
      (node (ref "SV14") (pin "10") (pinfunction "10_10") (pintype "passive"))
      (node (ref "U5") (pin "2") (pinfunction "SDI_2") (pintype "input"))
    )
    (net (code "246") (name "SDI_R") (class "Default")
      (node (ref "SV14") (pin "8") (pinfunction "8_8") (pintype "passive"))
      (node (ref "U1") (pin "2") (pinfunction "SDI_2") (pintype "input"))
    )
    (net (code "247") (name "unconnected-(SV13-Pad2)") (class "Default")
      (node (ref "SV13") (pin "2") (pinfunction "2_2") (pintype "passive"))
    )
    (net (code "248") (name "unconnected-(SV13-Pad4)") (class "Default")
      (node (ref "SV13") (pin "4") (pinfunction "4_4") (pintype "passive"))
    )
    (net (code "249") (name "unconnected-(SV13-Pad6)") (class "Default")
      (node (ref "SV13") (pin "6") (pinfunction "6_6") (pintype "passive"))
    )
    (net (code "250") (name "unconnected-(SV13-Pad8)") (class "Default")
      (node (ref "SV13") (pin "8") (pinfunction "8_8") (pintype "passive"))
    )
    (net (code "251") (name "unconnected-(SV13-Pad10)") (class "Default")
      (node (ref "SV13") (pin "10") (pinfunction "10_10") (pintype "passive"))
    )
    (net (code "252") (name "unconnected-(SV13-Pad12)") (class "Default")
      (node (ref "SV13") (pin "12") (pinfunction "12_12") (pintype "passive"))
    )
    (net (code "253") (name "unconnected-(SV13-Pad14)") (class "Default")
      (node (ref "SV13") (pin "14") (pinfunction "14_14") (pintype "passive"))
    )
    (net (code "254") (name "unconnected-(SV13-Pad16)") (class "Default")
      (node (ref "SV13") (pin "16") (pinfunction "16_16") (pintype "passive"))
    )
    (net (code "255") (name "unconnected-(U4-SDO-Pad22)") (class "Default")
      (node (ref "U4") (pin "22") (pinfunction "SDO_22") (pintype "output"))
    )
    (net (code "256") (name "unconnected-(U8-SDO-Pad22)") (class "Default")
      (node (ref "U8") (pin "22") (pinfunction "SDO_22") (pintype "output"))
    )
    (net (code "257") (name "unconnected-(U12-SDO-Pad22)") (class "Default")
      (node (ref "U12") (pin "22") (pinfunction "SDO_22") (pintype "output"))
    )
  )
)
